# transponder-7_0_0.net
KiCad netlist of a schematic drawn in EAGLE
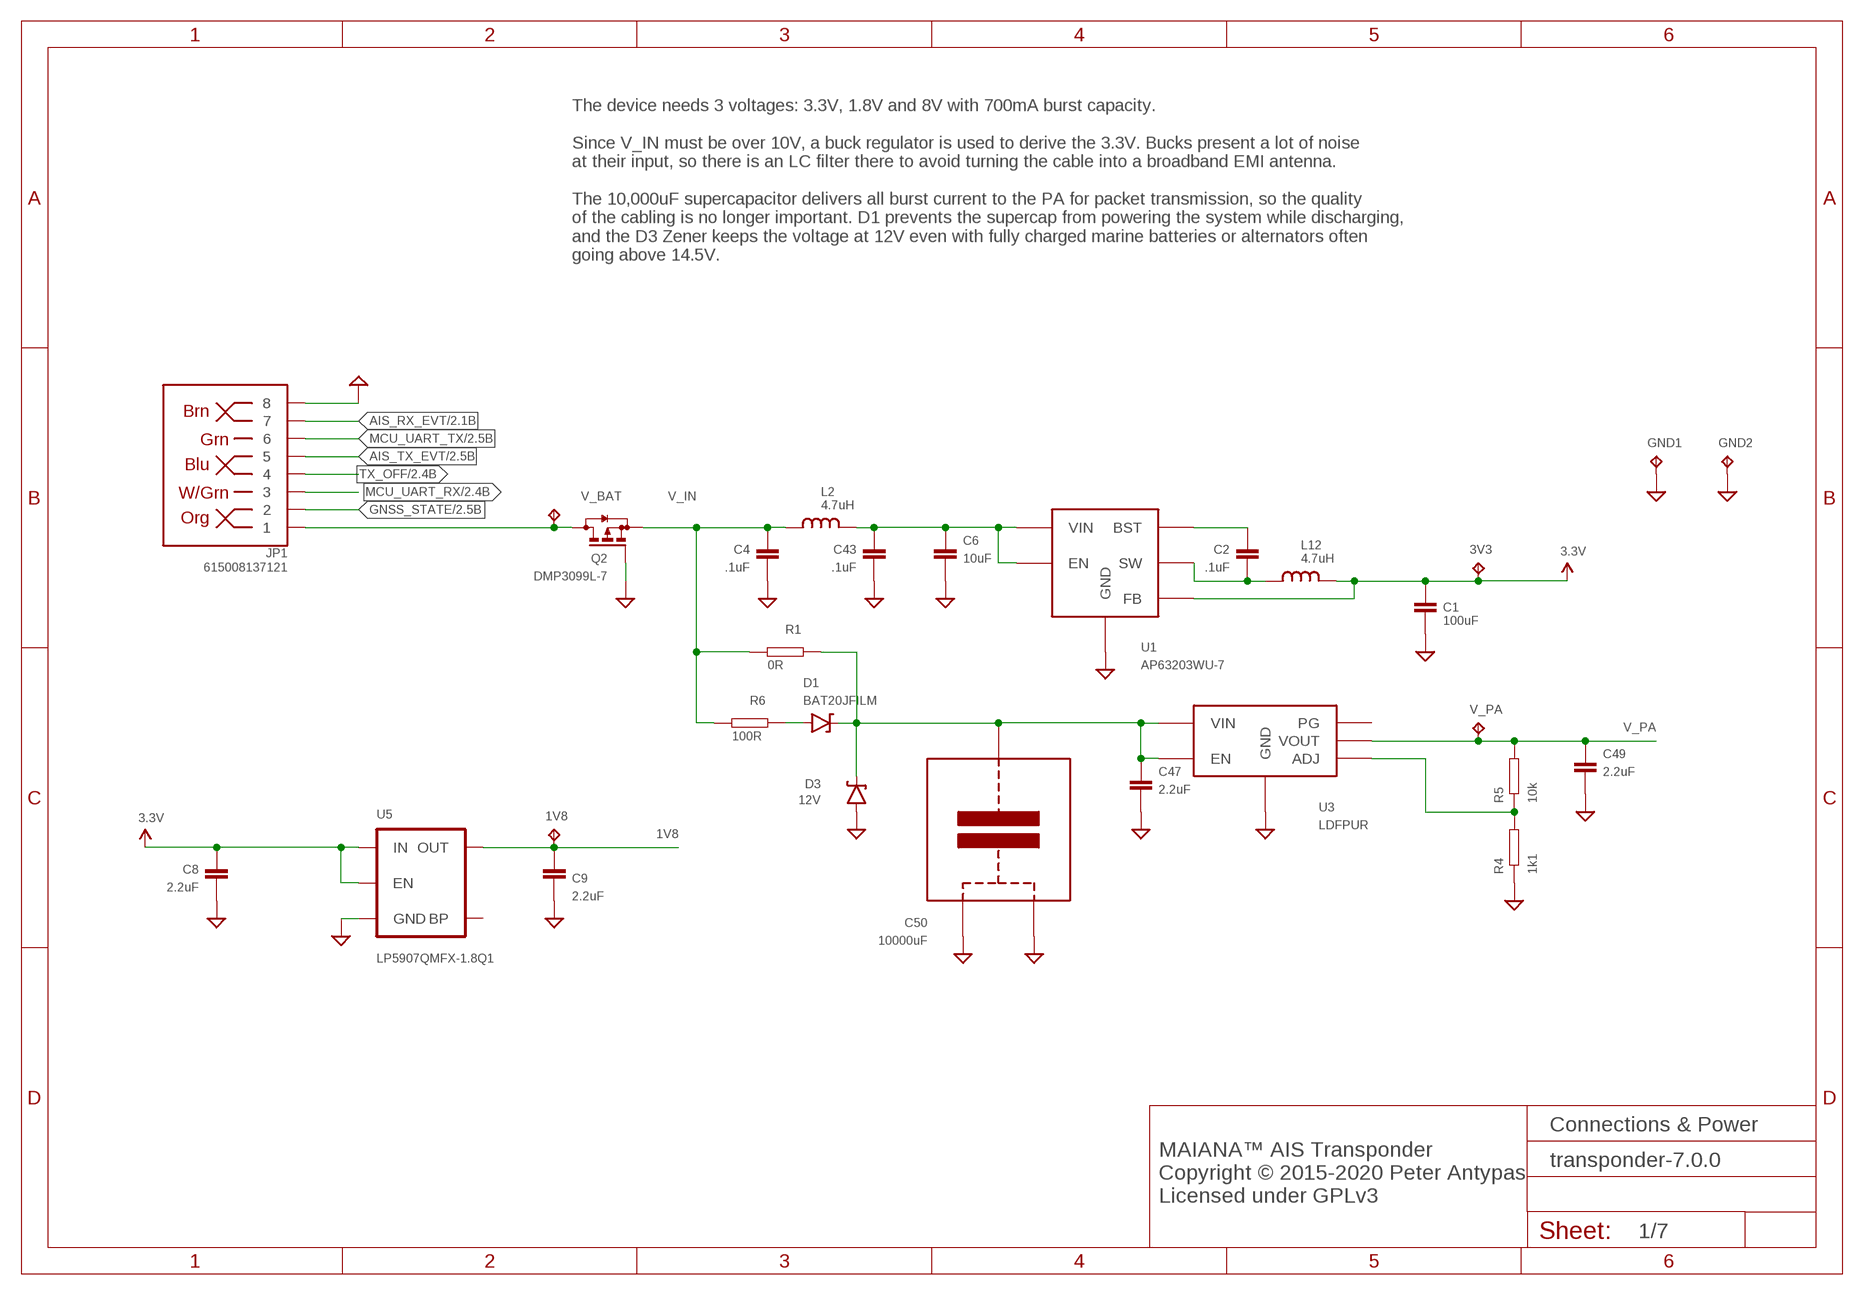
[diagram p0: schematic, sheet 1]
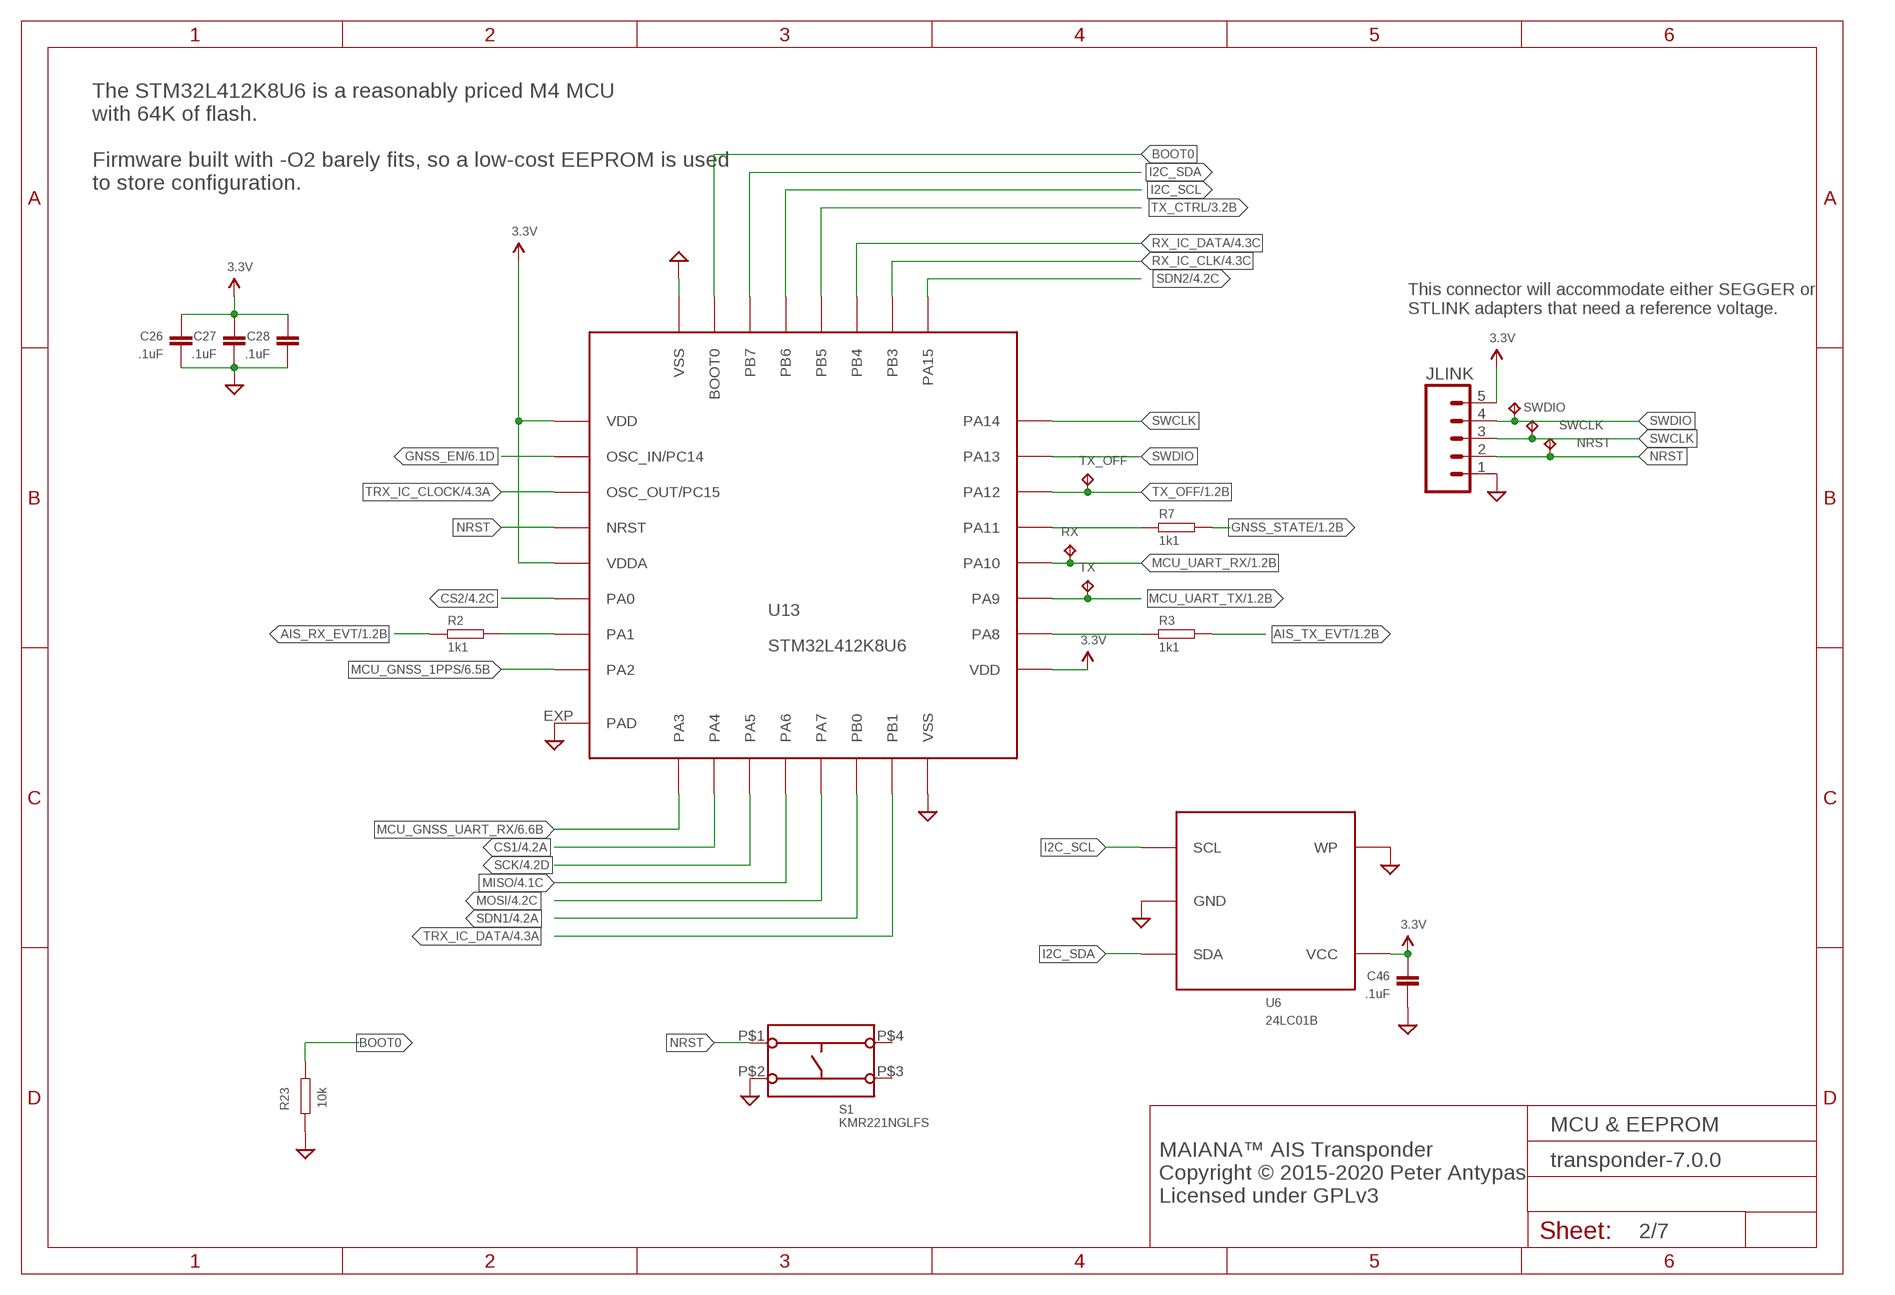
[diagram p1: schematic, sheet 2]
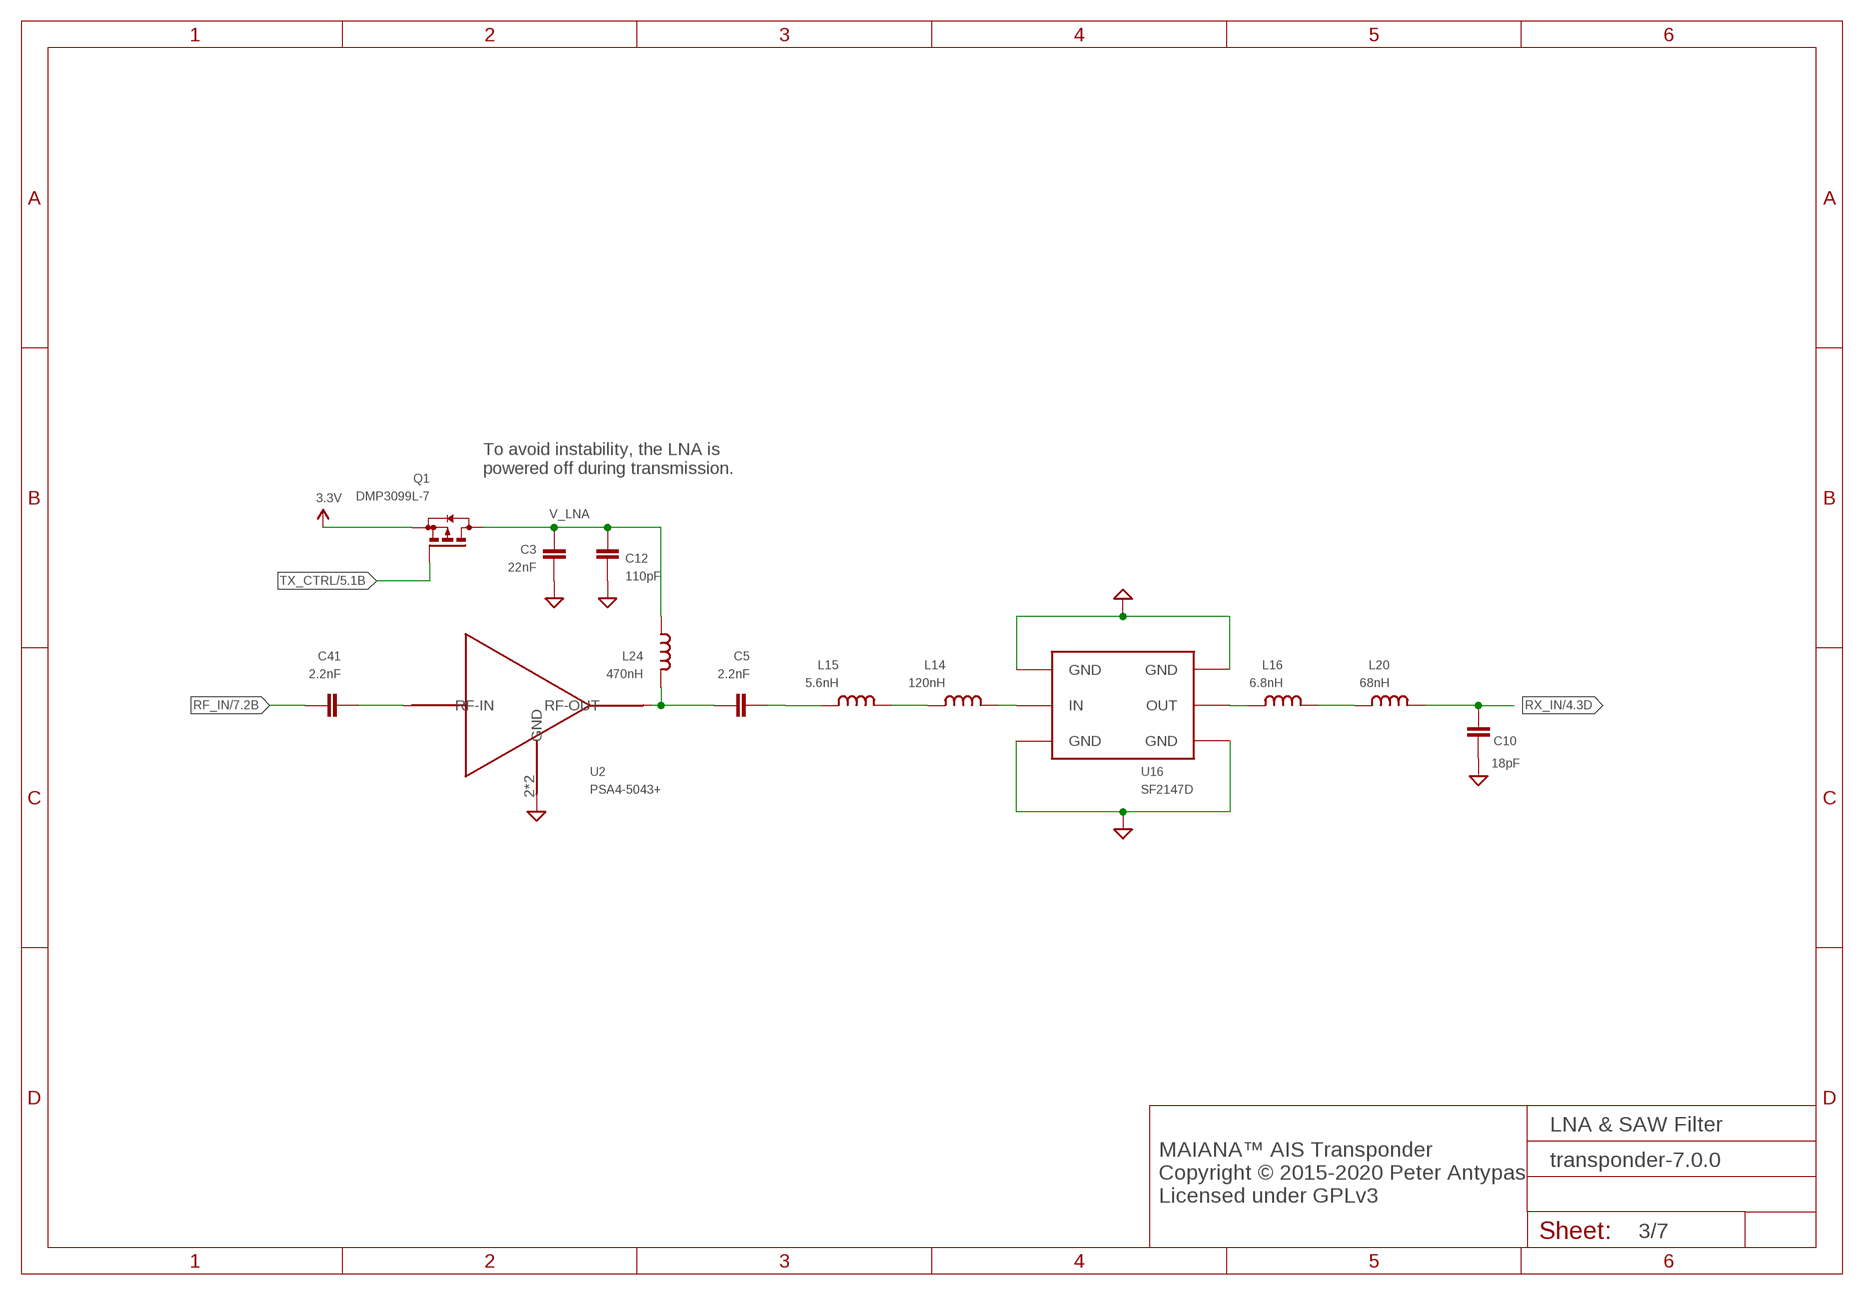
[diagram p2: schematic, sheet 3]
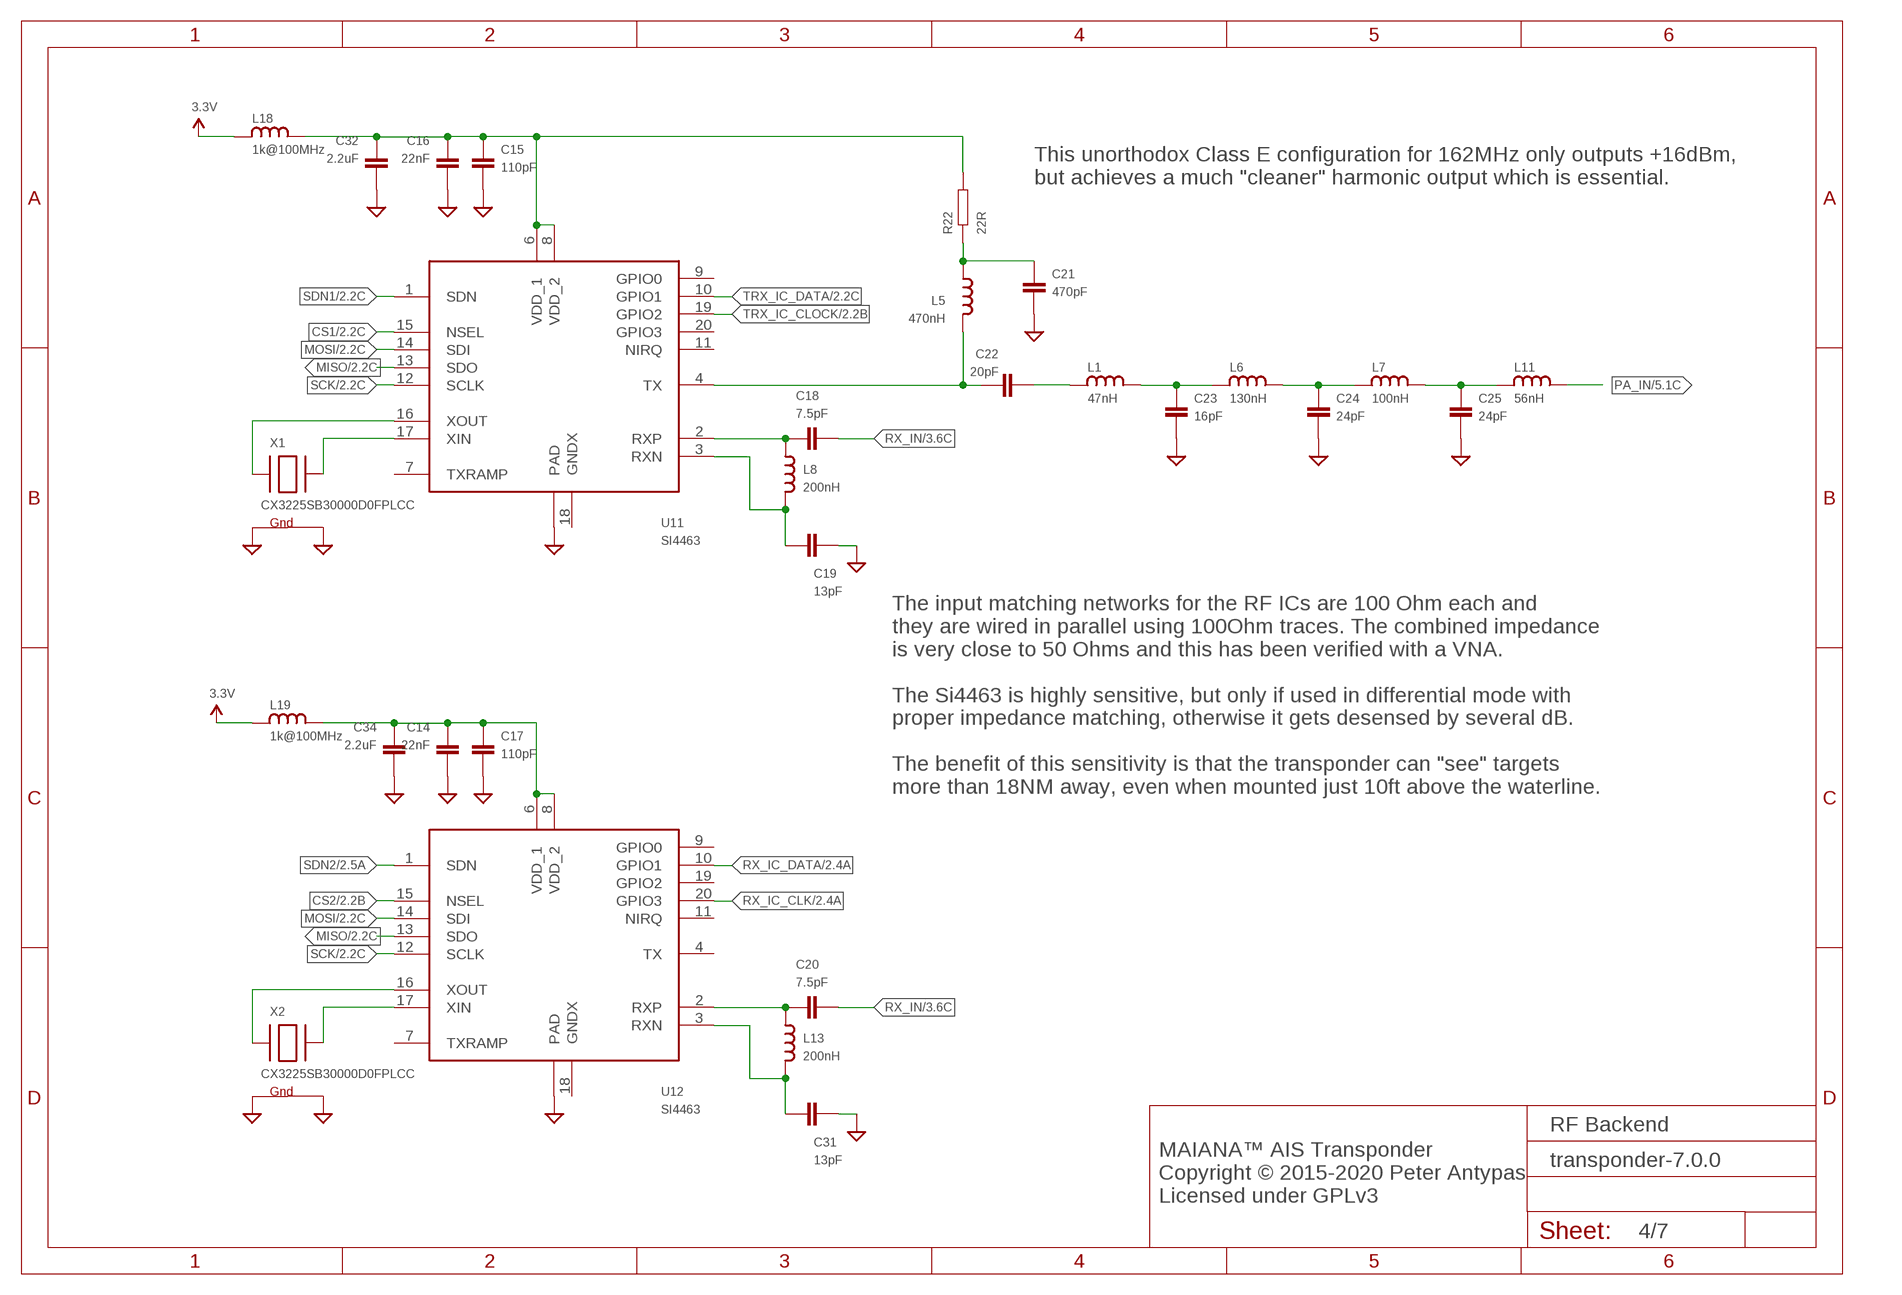
[diagram p3: schematic, sheet 4]
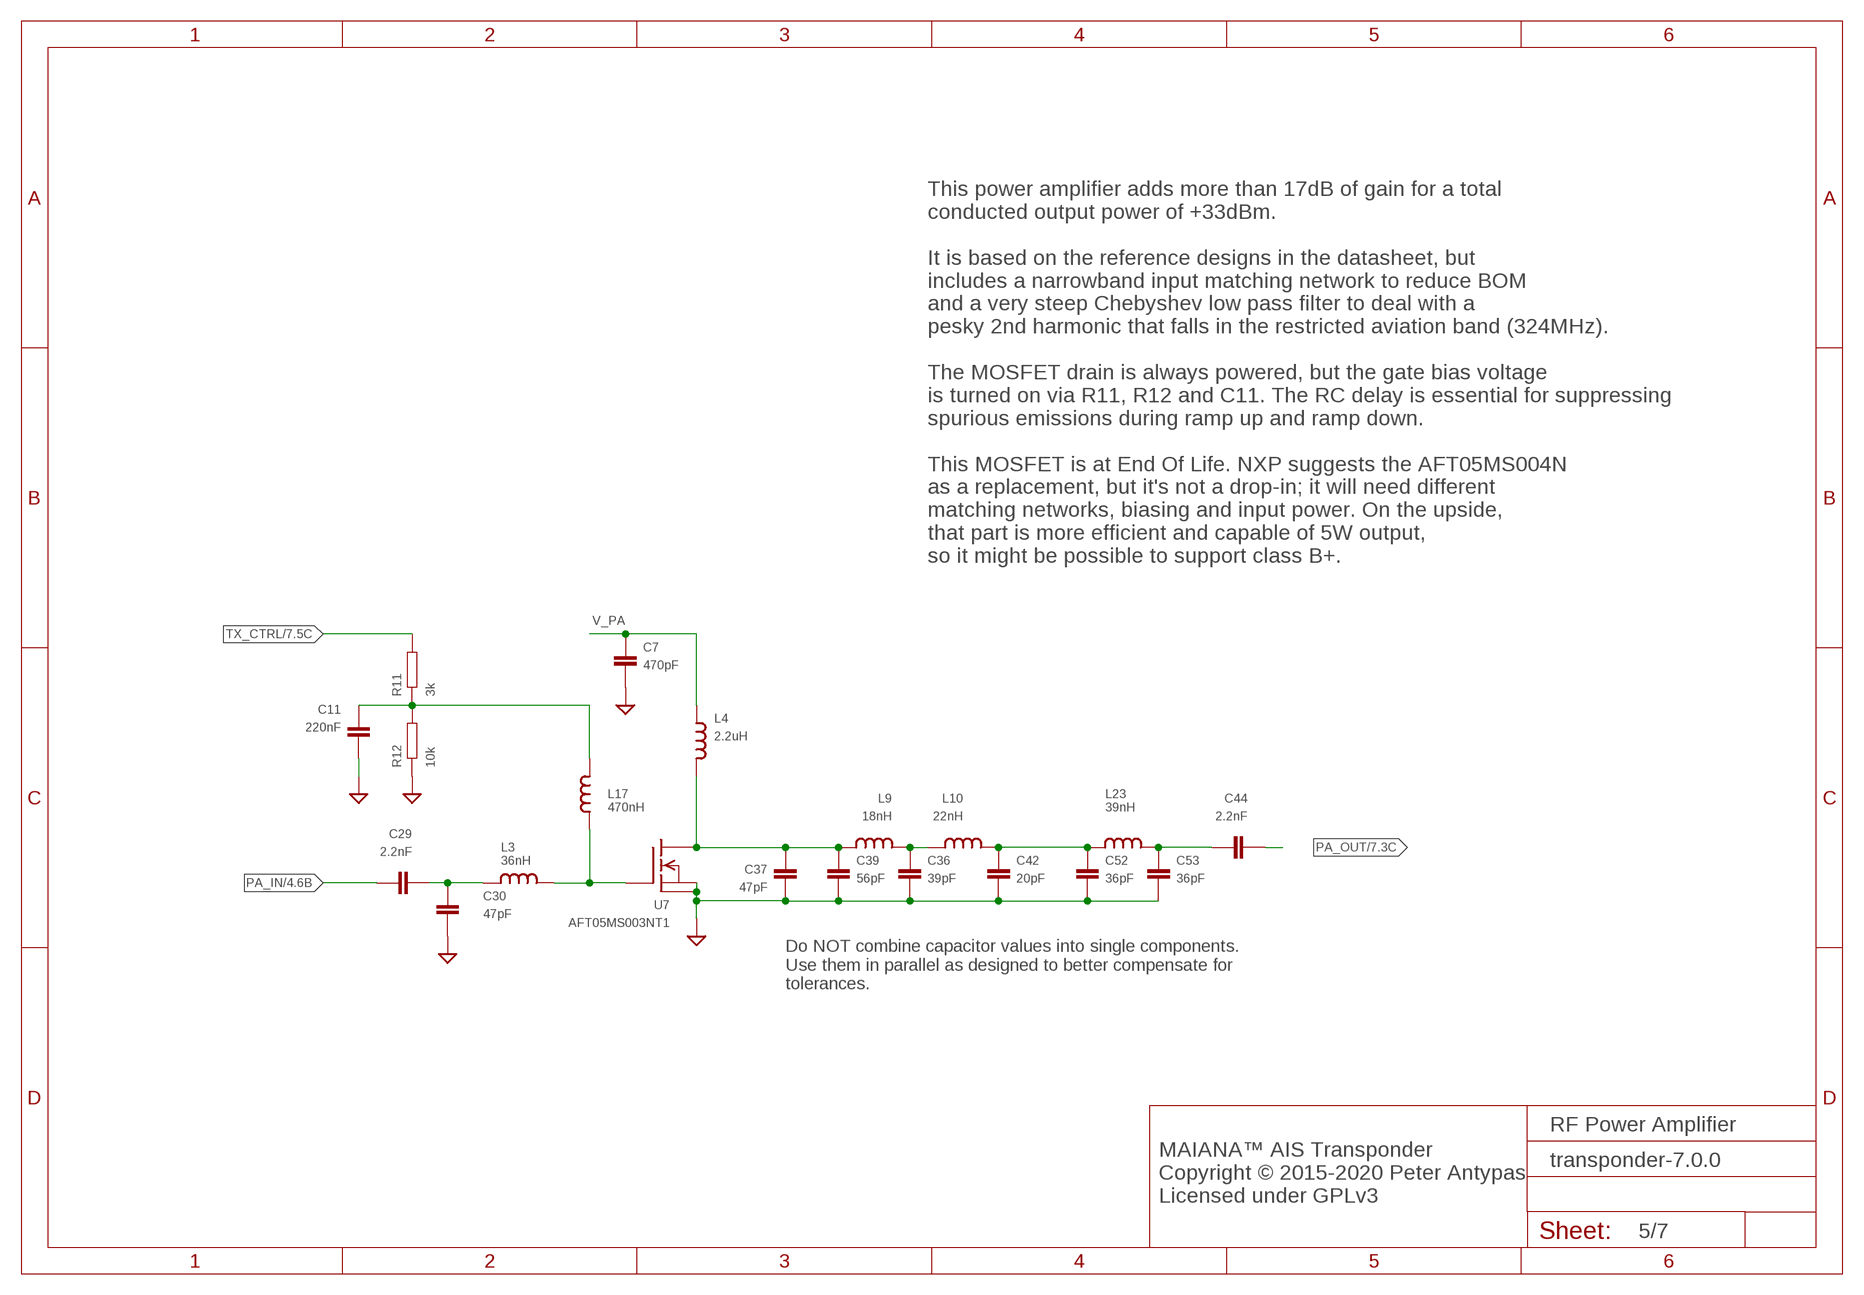
[diagram p4: schematic, sheet 5]
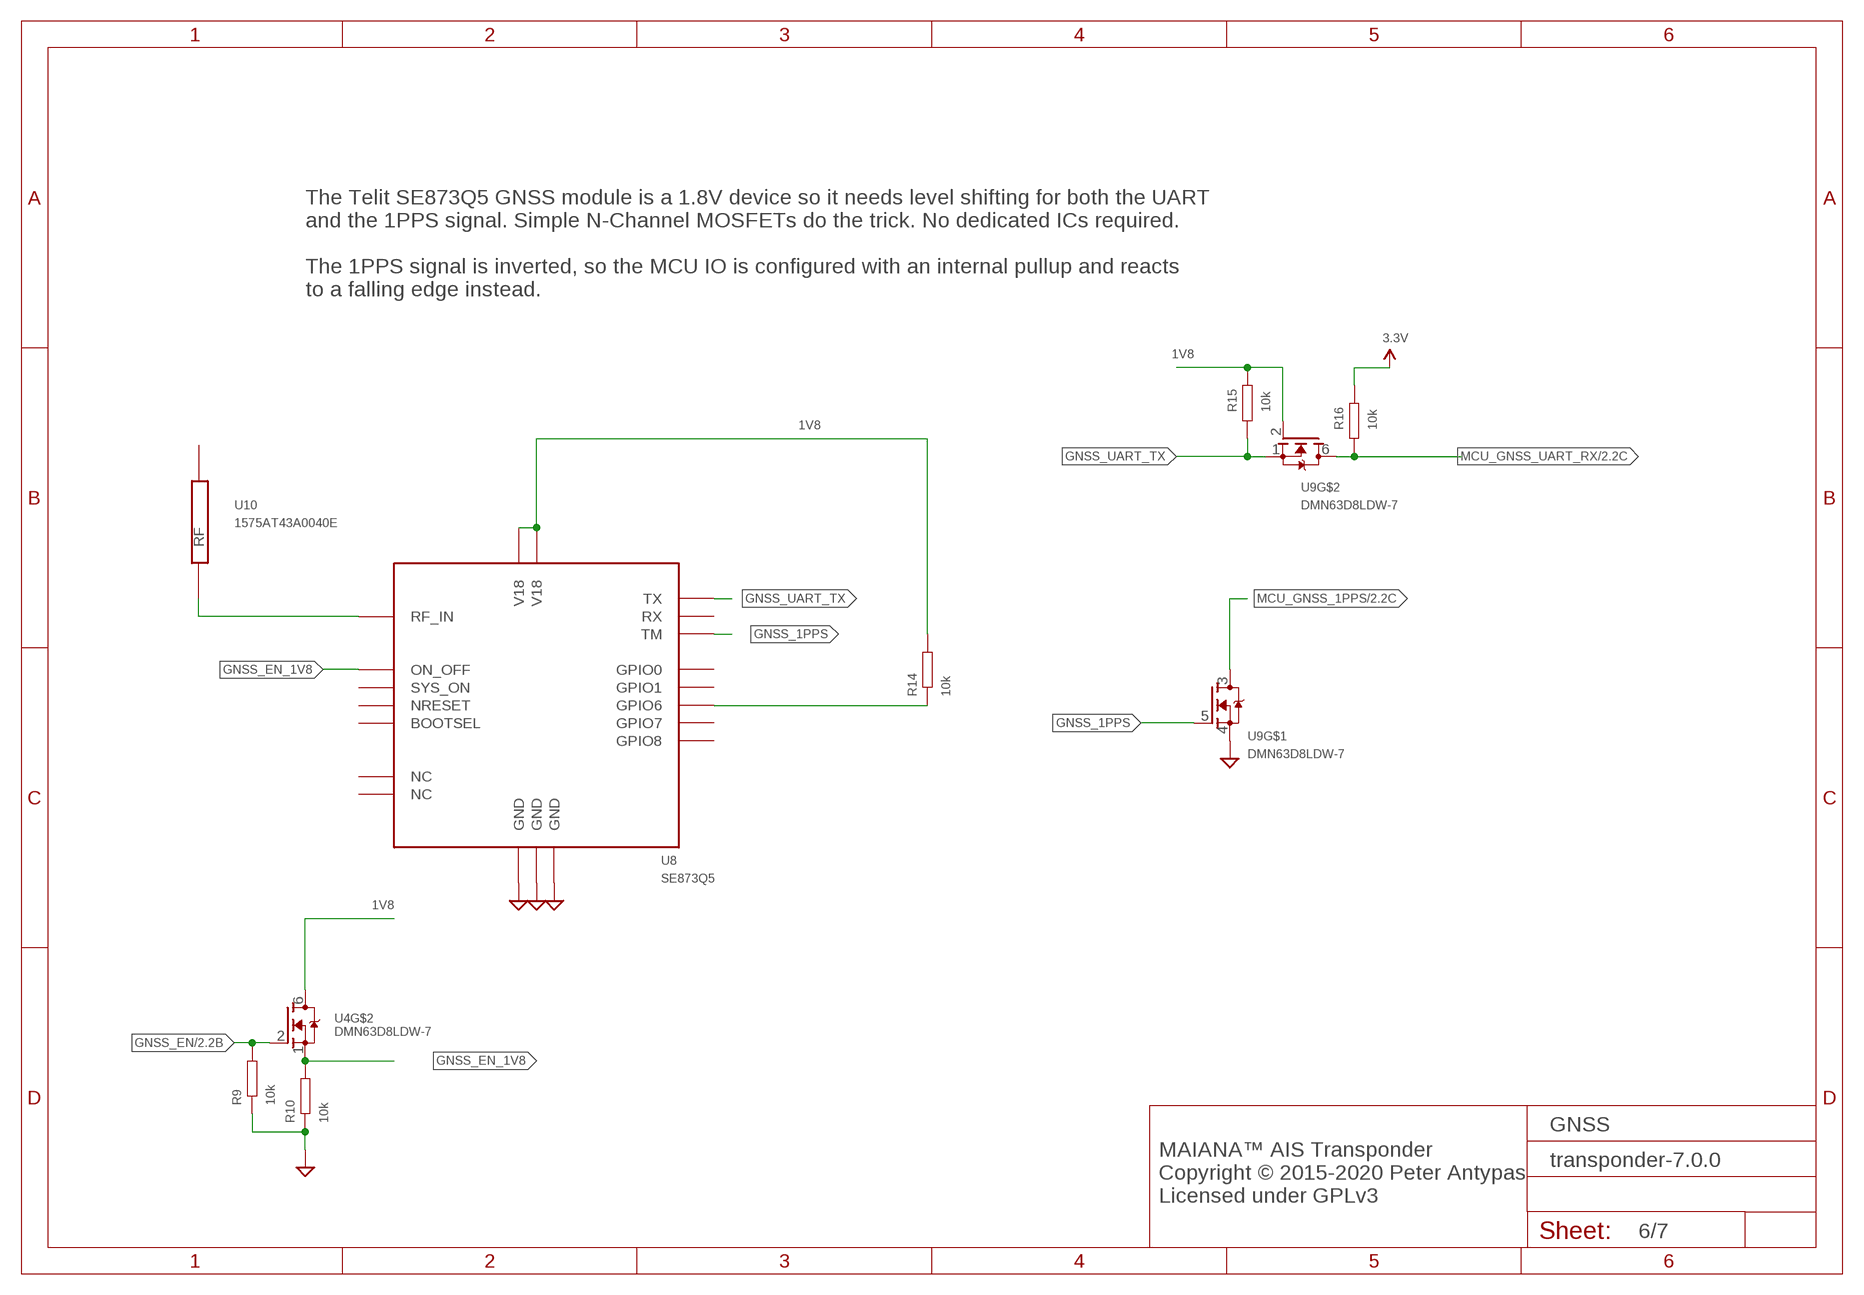
[diagram p5: schematic, sheet 6]
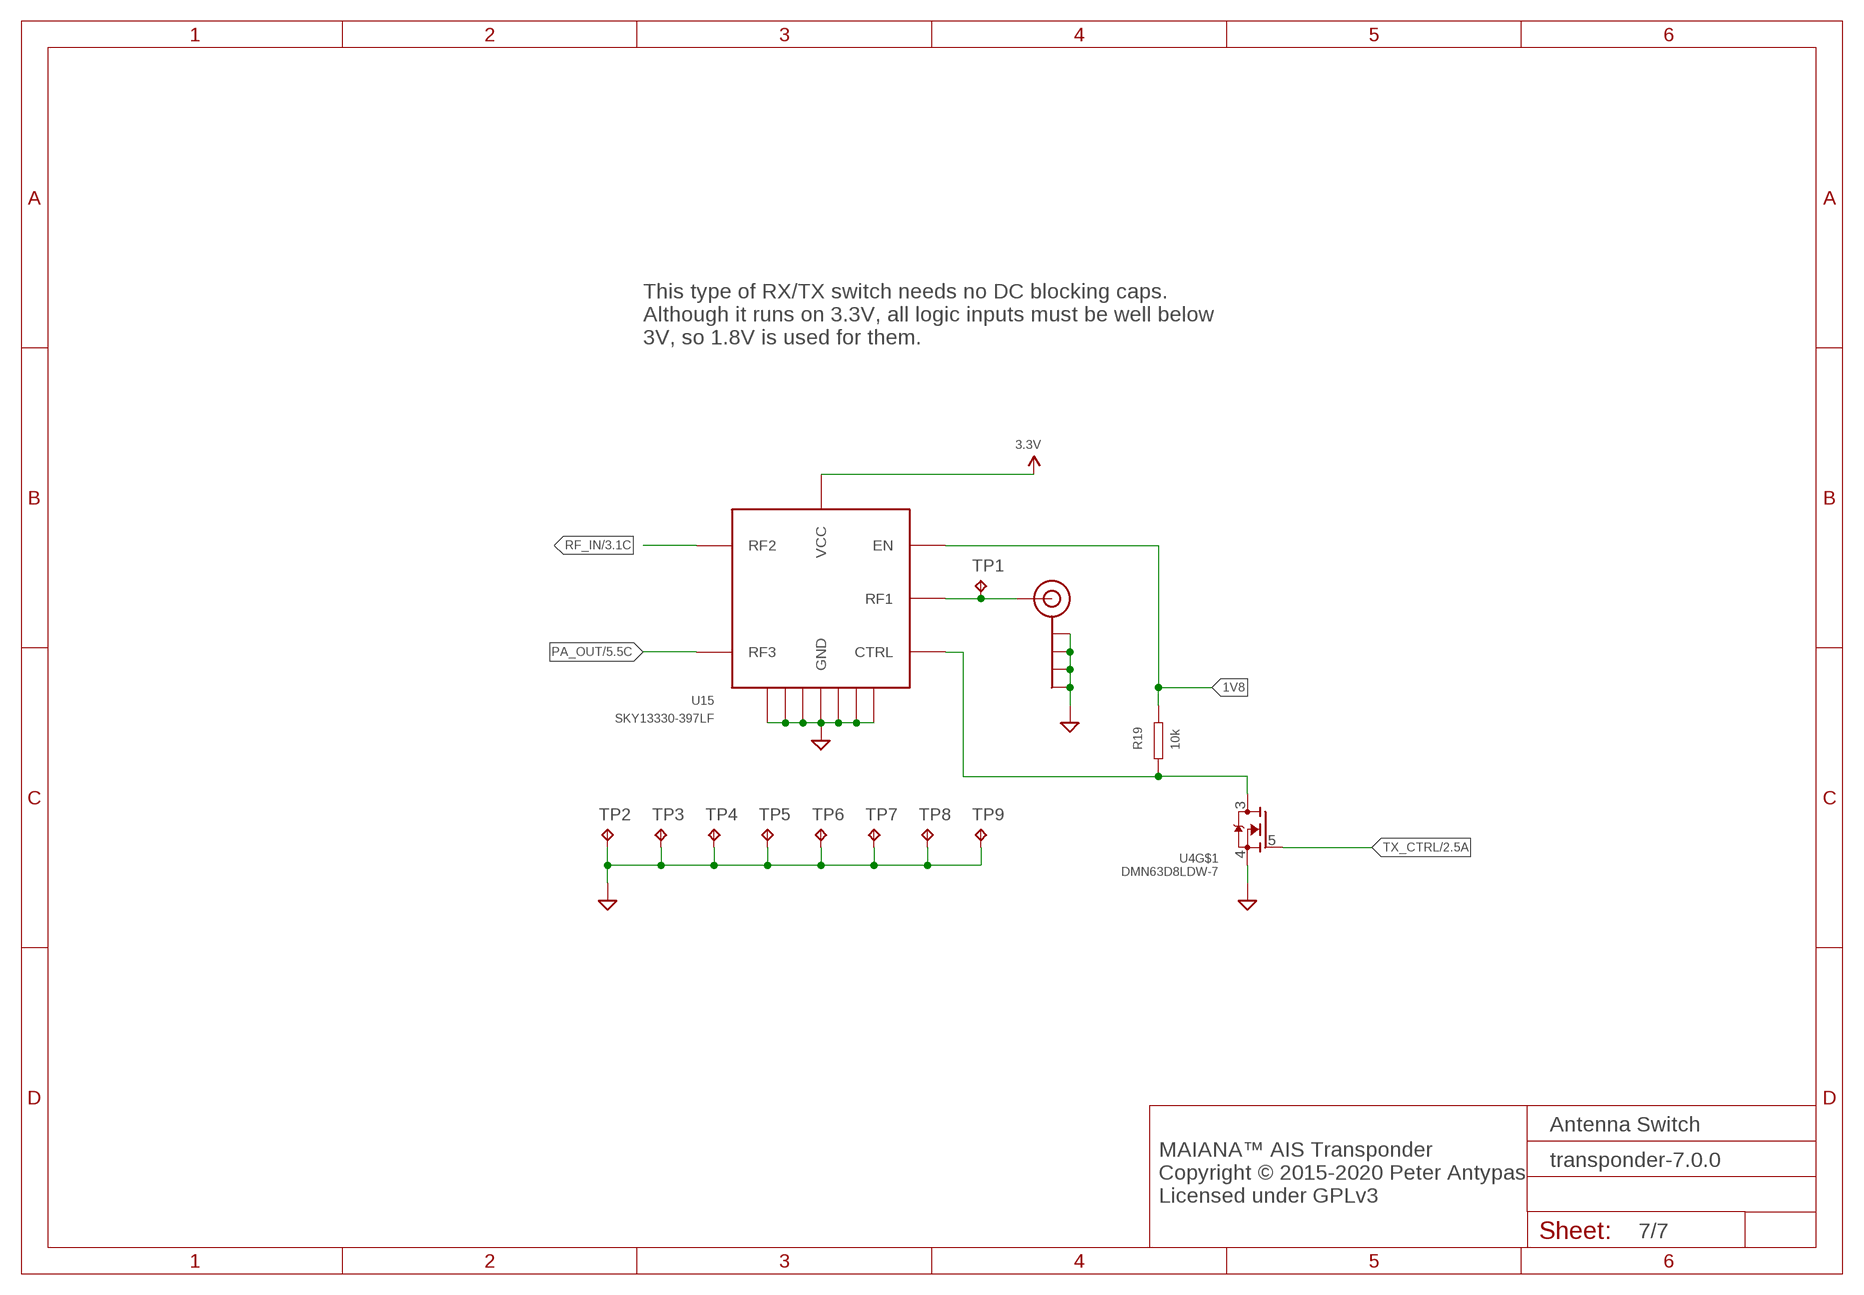
[diagram p6: schematic, sheet 7]

(export (version "E")
  (design (tool "Eeschema 10.0.6"))
  (components
    (comp (ref "1V8")
      (value "TPTP12R")
      (footprint "eagle-import:TP12R")
      (libsource (lib "eagle-import") (part "TPTP12R"))
    )
    (comp (ref "3V3")
      (value "TPTP12R")
      (footprint "eagle-import:TP12R")
      (libsource (lib "eagle-import") (part "TPTP12R"))
    )
    (comp (ref "C1")
      (value "100uF")
      (footprint "eagle-import:1206")
      (fields (field (name "PARTNO") "JMK316ABJ107ML-T"))
      (libsource (lib "eagle-import") (part "CAPACITOR1206"))
    )
    (comp (ref "C2")
      (value ".1uF")
      (footprint "eagle-import:0603")
      (fields (field (name "PARTNO") "EMK107B7104KAHT"))
      (libsource (lib "eagle-import") (part "CAPACITOR0603"))
    )
    (comp (ref "C4")
      (value ".1uF")
      (footprint "eagle-import:0603")
      (fields (field (name "PARTNO") "EMK107B7104KAHT"))
      (libsource (lib "eagle-import") (part "CAPACITOR0603"))
    )
    (comp (ref "C6")
      (value "10uF")
      (footprint "eagle-import:0805")
      (fields (field (name "PARTNO") " EMK212ABJ106KG-T"))
      (libsource (lib "eagle-import") (part "CAPACITOR0805"))
    )
    (comp (ref "C8")
      (value "2.2uF")
      (footprint "eagle-import:0603")
      (fields (field (name "PARTNO") "EMK107BJ225KA-T"))
      (libsource (lib "eagle-import") (part "CAPACITOR0603"))
    )
    (comp (ref "C9")
      (value "2.2uF")
      (footprint "eagle-import:0603")
      (fields (field (name "PARTNO") "EMK107BJ225KA-T"))
      (libsource (lib "eagle-import") (part "CAPACITOR0603"))
    )
    (comp (ref "C43")
      (value ".1uF")
      (footprint "eagle-import:0603")
      (fields (field (name "PARTNO") "EMK107B7104KAHT"))
      (libsource (lib "eagle-import") (part "CAPACITOR0603"))
    )
    (comp (ref "C47")
      (value "2.2uF")
      (footprint "eagle-import:0603")
      (fields (field (name "PARTNO") "EMK107BJ225KA-T"))
      (libsource (lib "eagle-import") (part "CAPACITOR0603"))
    )
    (comp (ref "C49")
      (value "2.2uF")
      (footprint "eagle-import:0603")
      (fields (field (name "PARTNO") "EMK107BJ225KA-T"))
      (libsource (lib "eagle-import") (part "CAPACITOR0603"))
    )
    (comp (ref "C50")
      (value "10000uF")
      (footprint "eagle-import:BZ05")
      (fields (field (name "PARTNO") "BZ05CA103ZSB"))
      (libsource (lib "eagle-import") (part "BZ05CA103ZSB"))
    )
    (comp (ref "D1")
      (value "BAT20JFILM")
      (footprint "eagle-import:SOD323")
      (fields (field (name "PARTNO") "BAT20JFILM"))
      (libsource (lib "eagle-import") (part "DIODE-SCHOTTKYSOD323"))
    )
    (comp (ref "D3")
      (value "12V")
      (footprint "eagle-import:SOD-323")
      (fields (field (name "PARTNO") "MM3Z12VST1G"))
      (libsource (lib "eagle-import") (part "DIODE-ZENER5.6V"))
    )
    (comp (ref "GND1")
      (value "TPTP16R")
      (footprint "eagle-import:TP16R")
      (libsource (lib "eagle-import") (part "TPTP16R"))
    )
    (comp (ref "GND2")
      (value "TPTP16R")
      (footprint "eagle-import:TP16R")
      (libsource (lib "eagle-import") (part "TPTP16R"))
    )
    (comp (ref "JP1")
      (value "615008137121")
      (footprint "eagle-import:RJ45-8")
      (fields (field (name "PARTNO") "‎615008137121‎"))
      (libsource (lib "eagle-import") (part "RJ45-8PTH"))
    )
    (comp (ref "L2")
      (value "4.7uH")
      (footprint "eagle-import:0805")
      (fields (field (name "PARTNO") "MLZ2012M4R7WT000"))
      (libsource (lib "eagle-import") (part "INDUCTOR0805"))
    )
    (comp (ref "L12")
      (value "4.7uH")
      (footprint "eagle-import:0805")
      (fields (field (name "PARTNO") "MLZ2012M4R7WT000"))
      (libsource (lib "eagle-import") (part "INDUCTOR0805"))
    )
    (comp (ref "Q2")
      (value "DMP3099L-7")
      (footprint "eagle-import:SOT23")
      (libsource (lib "eagle-import") (part "BSS84"))
    )
    (comp (ref "R1")
      (value "0R")
      (footprint "eagle-import:0603")
      (fields (field (name "PARTNO") "RC0603FR-070RL"))
      (libsource (lib "eagle-import") (part "RESISTOR0603"))
    )
    (comp (ref "R4")
      (value "1k1")
      (footprint "eagle-import:0603")
      (fields (field (name "PARTNO") "RC0603JR-071K1L"))
      (libsource (lib "eagle-import") (part "RESISTOR0603"))
    )
    (comp (ref "R5")
      (value "10k")
      (footprint "eagle-import:0603")
      (fields (field (name "PARTNO") "RC0603JR-0710KL"))
      (libsource (lib "eagle-import") (part "RESISTOR0603"))
    )
    (comp (ref "R6")
      (value "100R")
      (footprint "eagle-import:0603")
      (fields (field (name "PARTNO") "RC0603FR-07100RL"))
      (libsource (lib "eagle-import") (part "RESISTOR0603"))
    )
    (comp (ref "U1")
      (value "AP63203WU-7")
      (footprint "eagle-import:SOT23-6")
      (libsource (lib "eagle-import") (part "AP63203"))
    )
    (comp (ref "U3")
      (value "LDFPUR")
      (footprint "eagle-import:DFN-6")
      (libsource (lib "eagle-import") (part "LDF"))
    )
    (comp (ref "U5")
      (value "LP5907QMFX-1.8Q1")
      (footprint "eagle-import:SOT23-5")
      (fields (field (name "PARTNO") "LP5907QMFX-1.8Q1 "))
      (libsource (lib "eagle-import") (part "V_REG_LDOSMD"))
    )
    (comp (ref "V_BAT")
      (value "TPTP12R")
      (footprint "eagle-import:TP12R")
      (libsource (lib "eagle-import") (part "TPTP12R"))
    )
    (comp (ref "V_PA")
      (value "TPTP12R")
      (footprint "eagle-import:TP12R")
      (libsource (lib "eagle-import") (part "TPTP12R"))
    )
    (comp (ref "C3")
      (value "22nF")
      (footprint "eagle-import:0603")
      (fields (field (name "PARTNO") "GRM188R71E223KA01D"))
      (libsource (lib "eagle-import") (part "CAPACITOR0603"))
    )
    (comp (ref "C5")
      (value "2.2nF")
      (footprint "eagle-import:0603")
      (fields (field (name "PARTNO") "GRM1885C1H222JA01J"))
      (libsource (lib "eagle-import") (part "CAPACITOR0603"))
    )
    (comp (ref "C10")
      (value "18pF")
      (footprint "eagle-import:0603")
      (fields (field (name "PARTNO") "06035A180JAT4A"))
      (libsource (lib "eagle-import") (part "CAPACITOR0603"))
    )
    (comp (ref "C12")
      (value "110pF")
      (footprint "eagle-import:0603")
      (fields (field (name "PARTNO") "GRM1885C2A111JA01D"))
      (libsource (lib "eagle-import") (part "CAPACITOR0603"))
    )
    (comp (ref "C41")
      (value "2.2nF")
      (footprint "eagle-import:0603")
      (fields (field (name "PARTNO") "GRM1885C1H222JA01J"))
      (libsource (lib "eagle-import") (part "CAPACITOR0603"))
    )
    (comp (ref "L14")
      (value "120nH")
      (footprint "eagle-import:0603")
      (fields (field (name "PARTNO") "LQW18ASR12G0ZD"))
      (libsource (lib "eagle-import") (part "INDUCTOR0603"))
    )
    (comp (ref "L15")
      (value "5.6nH")
      (footprint "eagle-import:0603")
      (fields (field (name "PARTNO") "LQW18AN5N6G8ZD"))
      (libsource (lib "eagle-import") (part "INDUCTOR0603"))
    )
    (comp (ref "L16")
      (value "6.8nH")
      (footprint "eagle-import:0603")
      (fields (field (name "PARTNO") "LQW18AN6N8C10D"))
      (libsource (lib "eagle-import") (part "INDUCTOR0603"))
    )
    (comp (ref "L20")
      (value "68nH")
      (footprint "eagle-import:0603")
      (fields (field (name "PARTNO") "LQW18AN68NG00D"))
      (libsource (lib "eagle-import") (part "INDUCTOR0603"))
    )
    (comp (ref "L24")
      (value "470nH")
      (footprint "eagle-import:0603")
      (fields (field (name "PARTNO") "HK1608R47J-T"))
      (libsource (lib "eagle-import") (part "INDUCTOR0603"))
    )
    (comp (ref "Q1")
      (value "DMP3099L-7")
      (footprint "eagle-import:SOT23")
      (libsource (lib "eagle-import") (part "BSS84"))
    )
    (comp (ref "U2")
      (value "PSA4-5043+")
      (footprint "eagle-import:PSA4-5043+")
      (fields (field (name "MF") "Mini-Circuits"))
      (libsource (lib "eagle-import") (part "PSA4-5043+"))
    )
    (comp (ref "U16")
      (value "SF2147D")
      (footprint "eagle-import:SAW_FILTER1")
      (libsource (lib "eagle-import") (part "SF2147D"))
    )
    (comp (ref "C14")
      (value "22nF")
      (footprint "eagle-import:0603")
      (fields (field (name "PARTNO") "GRM188R71E223KA01D"))
      (libsource (lib "eagle-import") (part "CAPACITOR0603"))
    )
    (comp (ref "C15")
      (value "110pF")
      (footprint "eagle-import:0603")
      (fields (field (name "PARTNO") "GRM1885C2A111JA01D"))
      (libsource (lib "eagle-import") (part "CAPACITOR0603"))
    )
    (comp (ref "C16")
      (value "22nF")
      (footprint "eagle-import:0603")
      (fields (field (name "PARTNO") "GRM188R71E223KA01D"))
      (libsource (lib "eagle-import") (part "CAPACITOR0603"))
    )
    (comp (ref "C17")
      (value "110pF")
      (footprint "eagle-import:0603")
      (fields (field (name "PARTNO") "GRM1885C2A111JA01D"))
      (libsource (lib "eagle-import") (part "CAPACITOR0603"))
    )
    (comp (ref "C18")
      (value "7.5pF")
      (footprint "eagle-import:0603")
      (fields (field (name "PARTNO") "GRM1885C1H7R5DA01D"))
      (libsource (lib "eagle-import") (part "CAPACITOR0603"))
    )
    (comp (ref "C19")
      (value "13pF")
      (footprint "eagle-import:0603")
      (fields (field (name "PARTNO") "GRM1885C1H130JA01D"))
      (libsource (lib "eagle-import") (part "CAPACITOR0603"))
    )
    (comp (ref "C20")
      (value "7.5pF")
      (footprint "eagle-import:0603")
      (fields (field (name "PARTNO") "GRM1885C1H7R5DA01D"))
      (libsource (lib "eagle-import") (part "CAPACITOR0603"))
    )
    (comp (ref "C21")
      (value "470pF")
      (footprint "eagle-import:0603")
      (fields (field (name "PARTNO") "GRM1885C1H471JA01D"))
      (libsource (lib "eagle-import") (part "CAPACITOR0603"))
    )
    (comp (ref "C22")
      (value "20pF")
      (footprint "eagle-import:0603")
      (fields (field (name "PARTNO") "GRM1885C1H200JA01D"))
      (libsource (lib "eagle-import") (part "CAPACITOR0603"))
    )
    (comp (ref "C23")
      (value "16pF")
      (footprint "eagle-import:0603")
      (fields (field (name "PARTNO") "GCM1885C2A160JA16D"))
      (libsource (lib "eagle-import") (part "CAPACITOR0603"))
    )
    (comp (ref "C24")
      (value "24pF")
      (footprint "eagle-import:0603")
      (fields (field (name "PARTNO") "GRM1885C2A240JA01D"))
      (libsource (lib "eagle-import") (part "CAPACITOR0603"))
    )
    (comp (ref "C25")
      (value "24pF")
      (footprint "eagle-import:0603")
      (fields (field (name "PARTNO") "GRM1885C2A240JA01D"))
      (libsource (lib "eagle-import") (part "CAPACITOR0603"))
    )
    (comp (ref "C31")
      (value "13pF")
      (footprint "eagle-import:0603")
      (fields (field (name "PARTNO") "GRM1885C1H130JA01D"))
      (libsource (lib "eagle-import") (part "CAPACITOR0603"))
    )
    (comp (ref "C32")
      (value "2.2uF")
      (footprint "eagle-import:0603")
      (fields (field (name "PARTNO") "EMK107BJ225KA-T"))
      (libsource (lib "eagle-import") (part "CAPACITOR0603"))
    )
    (comp (ref "C34")
      (value "2.2uF")
      (footprint "eagle-import:0603")
      (fields (field (name "PARTNO") "EMK107BJ225KA-T"))
      (libsource (lib "eagle-import") (part "CAPACITOR0603"))
    )
    (comp (ref "L1")
      (value "47nH")
      (footprint "eagle-import:0603")
      (fields (field (name "PARTNO") "LQW18AN47NG00D"))
      (libsource (lib "eagle-import") (part "INDUCTOR0603"))
    )
    (comp (ref "L5")
      (value "470nH")
      (footprint "eagle-import:0603")
      (fields (field (name "PARTNO") "HK1608R47J-T"))
      (libsource (lib "eagle-import") (part "INDUCTOR0603"))
    )
    (comp (ref "L6")
      (value "130nH")
      (footprint "eagle-import:0603")
      (fields (field (name "PARTNO") "LQW18ANR13G00D"))
      (libsource (lib "eagle-import") (part "INDUCTOR0603"))
    )
    (comp (ref "L7")
      (value "100nH")
      (footprint "eagle-import:0603")
      (fields (field (name "PARTNO") "LQW18ANR10G00D"))
      (libsource (lib "eagle-import") (part "INDUCTOR0603"))
    )
    (comp (ref "L8")
      (value "200nH")
      (footprint "eagle-import:0603")
      (fields (field (name "PARTNO") "LQW18ANR20J00D"))
      (libsource (lib "eagle-import") (part "INDUCTOR0603"))
    )
    (comp (ref "L11")
      (value "56nH")
      (footprint "eagle-import:0603")
      (fields (field (name "PARTNO") "LQW18AN56NG00D"))
      (libsource (lib "eagle-import") (part "INDUCTOR0603"))
    )
    (comp (ref "L13")
      (value "200nH")
      (footprint "eagle-import:0603")
      (fields (field (name "PARTNO") "LQW18ANR20J00D"))
      (libsource (lib "eagle-import") (part "INDUCTOR0603"))
    )
    (comp (ref "L18")
      (value "1k@100MHz")
      (footprint "eagle-import:0603")
      (fields (field (name "PARTNO") "MPZ1608S102ATA00"))
      (libsource (lib "eagle-import") (part "INDUCTOR0603"))
    )
    (comp (ref "L19")
      (value "1k@100MHz")
      (footprint "eagle-import:0603")
      (fields (field (name "PARTNO") "MPZ1608S102ATA00"))
      (libsource (lib "eagle-import") (part "INDUCTOR0603"))
    )
    (comp (ref "R22")
      (value "22R")
      (footprint "eagle-import:0603")
      (fields (field (name "PARTNO") "RC0603JR-0722RL"))
      (libsource (lib "eagle-import") (part "RESISTOR0603"))
    )
    (comp (ref "U11")
      (value "SI4463")
      (footprint "eagle-import:SI4463")
      (fields (field (name "PARTNO") "SI4463-C2A-GMR"))
      (libsource (lib "eagle-import") (part "SI4463"))
    )
    (comp (ref "U12")
      (value "SI4463")
      (footprint "eagle-import:SI4463")
      (fields (field (name "PARTNO") "SI4463-C2A-GMR"))
      (libsource (lib "eagle-import") (part "SI4463"))
    )
    (comp (ref "X1")
      (value "CX3225SB30000D0FPLCC")
      (footprint "eagle-import:NX3225")
      (libsource (lib "eagle-import") (part "XTAL-4-3225"))
    )
    (comp (ref "X2")
      (value "CX3225SB30000D0FPLCC")
      (footprint "eagle-import:NX3225")
      (libsource (lib "eagle-import") (part "XTAL-4-3225"))
    )
    (comp (ref "C7")
      (value "470pF")
      (footprint "eagle-import:0603")
      (fields (field (name "PARTNO") "GRM1885C1H471JA01D"))
      (libsource (lib "eagle-import") (part "CAPACITOR0603"))
    )
    (comp (ref "C11")
      (value "220nF")
      (footprint "eagle-import:0603")
      (fields (field (name "PARTNO") "C0603C224K4RECAUTO"))
      (libsource (lib "eagle-import") (part "CAPACITOR0603"))
    )
    (comp (ref "C29")
      (value "2.2nF")
      (footprint "eagle-import:0603")
      (fields (field (name "PARTNO") "GRM1885C1H222JA01J"))
      (libsource (lib "eagle-import") (part "CAPACITOR0603"))
    )
    (comp (ref "C30")
      (value "47pF")
      (footprint "eagle-import:0603")
      (fields (field (name "PARTNO") "GRM1885C1H470JA01J"))
      (libsource (lib "eagle-import") (part "CAPACITOR0603"))
    )
    (comp (ref "C36")
      (value "39pF")
      (footprint "eagle-import:0603")
      (fields (field (name "PARTNO") "GRM1885C1H390JA01D"))
      (libsource (lib "eagle-import") (part "CAPACITOR0603"))
    )
    (comp (ref "C37")
      (value "47pF")
      (footprint "eagle-import:0603")
      (fields (field (name "PARTNO") "GRM1885C1H470JA01J"))
      (libsource (lib "eagle-import") (part "CAPACITOR0603"))
    )
    (comp (ref "C39")
      (value "56pF")
      (footprint "eagle-import:0603")
      (fields (field (name "PARTNO") "GRM1885C1H560JA01D"))
      (libsource (lib "eagle-import") (part "CAPACITOR0603"))
    )
    (comp (ref "C42")
      (value "20pF")
      (footprint "eagle-import:0603")
      (fields (field (name "PARTNO") "GRM1885C1H200JA01D"))
      (libsource (lib "eagle-import") (part "CAPACITOR0603"))
    )
    (comp (ref "C44")
      (value "2.2nF")
      (footprint "eagle-import:0603")
      (fields (field (name "PARTNO") "GRM1885C1H222JA01J"))
      (libsource (lib "eagle-import") (part "CAPACITOR0603"))
    )
    (comp (ref "C52")
      (value "36pF")
      (footprint "eagle-import:0603")
      (fields (field (name "PARTNO") "06035A360JAT2A"))
      (libsource (lib "eagle-import") (part "CAPACITOR0603"))
    )
    (comp (ref "C53")
      (value "36pF")
      (footprint "eagle-import:0603")
      (fields (field (name "PARTNO") "06035A360JAT2A"))
      (libsource (lib "eagle-import") (part "CAPACITOR0603"))
    )
    (comp (ref "L3")
      (value "36nH")
      (footprint "eagle-import:0603")
      (fields (field (name "PARTNO") "LQW18AN36NG00D"))
      (libsource (lib "eagle-import") (part "INDUCTOR0603"))
    )
    (comp (ref "L4")
      (value "2.2uH")
      (footprint "eagle-import:0805")
      (fields (field (name "PARTNO") "BRC2012T2R2MD"))
      (libsource (lib "eagle-import") (part "INDUCTOR0805"))
    )
    (comp (ref "L9")
      (value "18nH")
      (footprint "eagle-import:0603")
      (fields (field (name "PARTNO") "LQW18AN18NG00D"))
      (libsource (lib "eagle-import") (part "INDUCTOR0603"))
    )
    (comp (ref "L10")
      (value "22nH")
      (footprint "eagle-import:0603")
      (fields (field (name "PARTNO") "LQW18AN22NJ00D"))
      (libsource (lib "eagle-import") (part "INDUCTOR0603"))
    )
    (comp (ref "L17")
      (value "470nH")
      (footprint "eagle-import:0603")
      (fields (field (name "PARTNO") "HK1608R47J-T"))
      (libsource (lib "eagle-import") (part "INDUCTOR0603"))
    )
    (comp (ref "L23")
      (value "39nH")
      (footprint "eagle-import:0603")
      (fields (field (name "PARTNO") "LQW18AN39NG00D"))
      (libsource (lib "eagle-import") (part "INDUCTOR0603"))
    )
    (comp (ref "R11")
      (value "3k")
      (footprint "eagle-import:0603")
      (fields (field (name "PARTNO") "RC0603JR-073KL"))
      (libsource (lib "eagle-import") (part "RESISTOR0603"))
    )
    (comp (ref "R12")
      (value "10k")
      (footprint "eagle-import:0603")
      (fields (field (name "PARTNO") "RC0603JR-0710KL"))
      (libsource (lib "eagle-import") (part "RESISTOR0603"))
    )
    (comp (ref "U7")
      (value "AFT05MS003NT1")
      (footprint "eagle-import:SOT-89")
      (libsource (lib "eagle-import") (part "AFT0SMS003N"))
    )
    (comp (ref "R9")
      (value "10k")
      (footprint "eagle-import:0603")
      (fields (field (name "PARTNO") "RC0603JR-0710KL"))
      (libsource (lib "eagle-import") (part "RESISTOR0603"))
    )
    (comp (ref "R10")
      (value "10k")
      (footprint "eagle-import:0603")
      (fields (field (name "PARTNO") "RC0603JR-0710KL"))
      (libsource (lib "eagle-import") (part "RESISTOR0603"))
    )
    (comp (ref "R14")
      (value "10k")
      (footprint "eagle-import:0603")
      (fields (field (name "PARTNO") "RC0603JR-0710KL"))
      (libsource (lib "eagle-import") (part "RESISTOR0603"))
    )
    (comp (ref "R15")
      (value "10k")
      (footprint "eagle-import:0603")
      (fields (field (name "PARTNO") "RC0603JR-0710KL"))
      (libsource (lib "eagle-import") (part "RESISTOR0603"))
    )
    (comp (ref "R16")
      (value "10k")
      (footprint "eagle-import:0603")
      (fields (field (name "PARTNO") "RC0603JR-0710KL"))
      (libsource (lib "eagle-import") (part "RESISTOR0603"))
    )
    (comp (ref "U4")
      (value "DMN63D8LDW-7")
      (footprint "eagle-import:SOT363")
      (fields (field (name "PARTNO") "DMN63D8LDW-7"))
      (libsource (lib "eagle-import") (part "DMN63D8LDW"))
    )
    (comp (ref "U8")
      (value "SE873Q5")
      (footprint "eagle-import:SE873")
      (libsource (lib "eagle-import") (part "SE873"))
    )
    (comp (ref "U9")
      (value "DMN63D8LDW-7")
      (footprint "eagle-import:SOT363")
      (fields (field (name "PARTNO") "DMN63D8LDW-7"))
      (libsource (lib "eagle-import") (part "DMN63D8LDW"))
    )
    (comp (ref "U10")
      (value "1575AT43A0040E")
      (footprint "eagle-import:1575AT43A0040E")
      (libsource (lib "eagle-import") (part "1575AT43A0040E"))
    )
    (comp (ref "J$1")
      (value "SMA_EDGE")
      (footprint "eagle-import:SMA-EDGE")
      (libsource (lib "eagle-import") (part "SMA_EDGE"))
    )
    (comp (ref "R19")
      (value "10k")
      (footprint "eagle-import:0603")
      (fields (field (name "PARTNO") "RC0603JR-0710KL"))
      (libsource (lib "eagle-import") (part "RESISTOR0603"))
    )
    (comp (ref "TP1")
      (value "TPTP10R")
      (footprint "eagle-import:TP10R")
      (libsource (lib "eagle-import") (part "TPTP10R"))
    )
    (comp (ref "TP2")
      (value "TPTP08R")
      (footprint "eagle-import:TP08R")
      (libsource (lib "eagle-import") (part "TPTP08R"))
    )
    (comp (ref "TP3")
      (value "TPTP08R")
      (footprint "eagle-import:TP08R")
      (libsource (lib "eagle-import") (part "TPTP08R"))
    )
    (comp (ref "TP4")
      (value "TPTP08R")
      (footprint "eagle-import:TP08R")
      (libsource (lib "eagle-import") (part "TPTP08R"))
    )
    (comp (ref "TP5")
      (value "TPTP08R")
      (footprint "eagle-import:TP08R")
      (libsource (lib "eagle-import") (part "TPTP08R"))
    )
    (comp (ref "TP6")
      (value "TPTP08R")
      (footprint "eagle-import:TP08R")
      (libsource (lib "eagle-import") (part "TPTP08R"))
    )
    (comp (ref "TP7")
      (value "TPTP08R")
      (footprint "eagle-import:TP08R")
      (libsource (lib "eagle-import") (part "TPTP08R"))
    )
    (comp (ref "TP8")
      (value "TPTP08R")
      (footprint "eagle-import:TP08R")
      (libsource (lib "eagle-import") (part "TPTP08R"))
    )
    (comp (ref "TP9")
      (value "TPTP08R")
      (footprint "eagle-import:TP08R")
      (libsource (lib "eagle-import") (part "TPTP08R"))
    )
    (comp (ref "U15")
      (value "SKY13330-397LF")
      (footprint "eagle-import:QFN12")
      (libsource (lib "eagle-import") (part "SKYWORKS-13330397LF"))
    )
    (comp (ref "C26")
      (value ".1uF")
      (footprint "eagle-import:0603")
      (fields (field (name "PARTNO") "EMK107B7104KAHT"))
      (libsource (lib "eagle-import") (part "CAPACITOR0603"))
    )
    (comp (ref "C27")
      (value ".1uF")
      (footprint "eagle-import:0603")
      (fields (field (name "PARTNO") "EMK107B7104KAHT"))
      (libsource (lib "eagle-import") (part "CAPACITOR0603"))
    )
    (comp (ref "C28")
      (value ".1uF")
      (footprint "eagle-import:0603")
      (fields (field (name "PARTNO") "EMK107B7104KAHT"))
      (libsource (lib "eagle-import") (part "CAPACITOR0603"))
    )
    (comp (ref "C46")
      (value ".1uF")
      (footprint "eagle-import:0603")
      (fields (field (name "PARTNO") "EMK107B7104KAHT"))
      (libsource (lib "eagle-import") (part "CAPACITOR0603"))
    )
    (comp (ref "JLINK")
      (value "M05PTH")
      (footprint "eagle-import:1X05")
      (libsource (lib "eagle-import") (part "M05PTH"))
    )
    (comp (ref "NRST")
      (value "TPTP12R")
      (footprint "eagle-import:TP12R")
      (libsource (lib "eagle-import") (part "TPTP12R"))
    )
    (comp (ref "R2")
      (value "1k1")
      (footprint "eagle-import:0603")
      (fields (field (name "PARTNO") "RC0603JR-071K1L"))
      (libsource (lib "eagle-import") (part "RESISTOR0603"))
    )
    (comp (ref "R3")
      (value "1k1")
      (footprint "eagle-import:0603")
      (fields (field (name "PARTNO") "RC0603JR-071K1L"))
      (libsource (lib "eagle-import") (part "RESISTOR0603"))
    )
    (comp (ref "R7")
      (value "1k1")
      (footprint "eagle-import:0603")
      (fields (field (name "PARTNO") "RC0603JR-071K1L"))
      (libsource (lib "eagle-import") (part "RESISTOR0603"))
    )
    (comp (ref "R23")
      (value "10k")
      (footprint "eagle-import:0603")
      (fields (field (name "PARTNO") "RC0603JR-0710KL"))
      (libsource (lib "eagle-import") (part "RESISTOR0603"))
    )
    (comp (ref "RX")
      (value "TPTP12R")
      (footprint "eagle-import:TP12R")
      (libsource (lib "eagle-import") (part "TPTP12R"))
    )
    (comp (ref "S1")
      (value "KMR221NGLFS")
      (footprint "eagle-import:KMR221NGLFS")
      (libsource (lib "eagle-import") (part "KMR221NGLFS"))
    )
    (comp (ref "SWCLK")
      (value "TPTP12R")
      (footprint "eagle-import:TP12R")
      (libsource (lib "eagle-import") (part "TPTP12R"))
    )
    (comp (ref "SWDIO")
      (value "TPTP12R")
      (footprint "eagle-import:TP12R")
      (libsource (lib "eagle-import") (part "TPTP12R"))
    )
    (comp (ref "TX")
      (value "TPTP12R")
      (footprint "eagle-import:TP12R")
      (libsource (lib "eagle-import") (part "TPTP12R"))
    )
    (comp (ref "TX_OFF")
      (value "TPTP12R")
      (footprint "eagle-import:TP12R")
      (libsource (lib "eagle-import") (part "TPTP12R"))
    )
    (comp (ref "U6")
      (value "24LC01B")
      (footprint "eagle-import:SOT23-5")
      (fields (field (name "PARTNO") "24LC01BT-I/OT"))
      (libsource (lib "eagle-import") (part "24LC01B"))
    )
    (comp (ref "U13")
      (value "STM32L412K8U6")
      (footprint "eagle-import:QFN32")
      (libsource (lib "eagle-import") (part "STM32L432KXXX"))
    )
  )
  (nets
    (net (code "1") (name "1V8") (class "Default")
      (node (ref "1V8") (pin "TP") (pinfunction "TP_TP") (pintype "input"))
      (node (ref "C9") (pin "P$1") (pinfunction "1_P$1") (pintype "passive"))
      (node (ref "R14") (pin "P$2") (pinfunction "P$2_P$2") (pintype "passive"))
      (node (ref "R15") (pin "P$2") (pinfunction "P$2_P$2") (pintype "passive"))
      (node (ref "R19") (pin "P$2") (pinfunction "P$2_P$2") (pintype "passive"))
      (node (ref "U15") (pin "P$8") (pinfunction "EN_P$8") (pintype "bidirectional"))
      (node (ref "U4") (pin "6") (pinfunction "D_6") (pintype "bidirectional"))
      (node (ref "U5") (pin "5") (pinfunction "OUT_5") (pintype "passive"))
      (node (ref "U8") (pin "P$19") (pinfunction "V18_P$19") (pintype "bidirectional"))
      (node (ref "U8") (pin "P$3") (pinfunction "V18_P$3") (pintype "bidirectional"))
      (node (ref "U9") (pin "2") (pinfunction "G_2") (pintype "bidirectional"))
    )
    (net (code "2") (name "3.3V") (class "Default")
      (node (ref "3V3") (pin "TP") (pinfunction "TP_TP") (pintype "input"))
      (node (ref "C1") (pin "P$1") (pinfunction "1_P$1") (pintype "passive"))
      (node (ref "C26") (pin "P$1") (pinfunction "1_P$1") (pintype "passive"))
      (node (ref "C27") (pin "P$1") (pinfunction "1_P$1") (pintype "passive"))
      (node (ref "C28") (pin "P$1") (pinfunction "1_P$1") (pintype "passive"))
      (node (ref "C46") (pin "P$1") (pinfunction "1_P$1") (pintype "passive"))
      (node (ref "C8") (pin "P$1") (pinfunction "1_P$1") (pintype "passive"))
      (node (ref "JLINK") (pin "5") (pinfunction "5_5") (pintype "passive"))
      (node (ref "L12") (pin "P$2") (pinfunction "2_P$2") (pintype "passive"))
      (node (ref "L18") (pin "P$1") (pinfunction "1_P$1") (pintype "passive"))
      (node (ref "L19") (pin "P$1") (pinfunction "1_P$1") (pintype "passive"))
      (node (ref "Q1") (pin "2") (pinfunction "S_2") (pintype "passive"))
      (node (ref "R16") (pin "P$2") (pinfunction "P$2_P$2") (pintype "passive"))
      (node (ref "U1") (pin "1") (pinfunction "FB_1") (pintype "bidirectional"))
      (node (ref "U13") (pin "1") (pinfunction "VDD_1") (pintype "bidirectional"))
      (node (ref "U13") (pin "17") (pinfunction "VDD_17") (pintype "bidirectional"))
      (node (ref "U13") (pin "5") (pinfunction "VDDA_5") (pintype "bidirectional"))
      (node (ref "U15") (pin "P$9") (pinfunction "VCC_P$9") (pintype "bidirectional"))
      (node (ref "U5") (pin "1") (pinfunction "IN_1") (pintype "input"))
      (node (ref "U5") (pin "3") (pinfunction "EN_3") (pintype "input"))
      (node (ref "U6") (pin "4") (pinfunction "VCC_4") (pintype "bidirectional"))
    )
    (net (code "3") (name "AIS_RX_EVT") (class "Default")
      (node (ref "JP1") (pin "7") (pinfunction "7_7") (pintype "bidirectional"))
      (node (ref "R2") (pin "P$1") (pinfunction "P$1_P$1") (pintype "passive"))
    )
    (net (code "4") (name "AIS_TX_EVT") (class "Default")
      (node (ref "JP1") (pin "5") (pinfunction "5_5") (pintype "bidirectional"))
      (node (ref "R3") (pin "P$2") (pinfunction "P$2_P$2") (pintype "passive"))
    )
    (net (code "5") (name "BOOT0") (class "Default")
      (node (ref "R23") (pin "P$1") (pinfunction "P$1_P$1") (pintype "passive"))
      (node (ref "U13") (pin "31") (pinfunction "BOOT0_31") (pintype "bidirectional"))
    )
    (net (code "6") (name "CS1") (class "Default")
      (node (ref "U11") (pin "15") (pinfunction "NSEL_15") (pintype "input"))
      (node (ref "U13") (pin "10") (pinfunction "PA4_10") (pintype "bidirectional"))
    )
    (net (code "7") (name "CS2") (class "Default")
      (node (ref "U12") (pin "15") (pinfunction "NSEL_15") (pintype "input"))
      (node (ref "U13") (pin "6") (pinfunction "PA0_6") (pintype "bidirectional"))
    )
    (net (code "8") (name "GND") (class "Default")
      (node (ref "C1") (pin "P$2") (pinfunction "2_P$2") (pintype "passive"))
      (node (ref "C10") (pin "P$1") (pinfunction "1_P$1") (pintype "passive"))
      (node (ref "C11") (pin "P$2") (pinfunction "2_P$2") (pintype "passive"))
      (node (ref "C12") (pin "P$1") (pinfunction "1_P$1") (pintype "passive"))
      (node (ref "C14") (pin "P$2") (pinfunction "2_P$2") (pintype "passive"))
      (node (ref "C15") (pin "P$2") (pinfunction "2_P$2") (pintype "passive"))
      (node (ref "C16") (pin "P$2") (pinfunction "2_P$2") (pintype "passive"))
      (node (ref "C17") (pin "P$2") (pinfunction "2_P$2") (pintype "passive"))
      (node (ref "C19") (pin "P$1") (pinfunction "1_P$1") (pintype "passive"))
      (node (ref "C21") (pin "P$2") (pinfunction "2_P$2") (pintype "passive"))
      (node (ref "C23") (pin "P$2") (pinfunction "2_P$2") (pintype "passive"))
      (node (ref "C24") (pin "P$2") (pinfunction "2_P$2") (pintype "passive"))
      (node (ref "C25") (pin "P$2") (pinfunction "2_P$2") (pintype "passive"))
      (node (ref "C26") (pin "P$2") (pinfunction "2_P$2") (pintype "passive"))
      (node (ref "C27") (pin "P$2") (pinfunction "2_P$2") (pintype "passive"))
      (node (ref "C28") (pin "P$2") (pinfunction "2_P$2") (pintype "passive"))
      (node (ref "C3") (pin "P$2") (pinfunction "2_P$2") (pintype "passive"))
      (node (ref "C30") (pin "P$2") (pinfunction "2_P$2") (pintype "passive"))
      (node (ref "C31") (pin "P$1") (pinfunction "1_P$1") (pintype "passive"))
      (node (ref "C32") (pin "P$2") (pinfunction "2_P$2") (pintype "passive"))
      (node (ref "C34") (pin "P$2") (pinfunction "2_P$2") (pintype "passive"))
      (node (ref "C36") (pin "P$2") (pinfunction "2_P$2") (pintype "passive"))
      (node (ref "C37") (pin "P$2") (pinfunction "2_P$2") (pintype "passive"))
      (node (ref "C39") (pin "P$2") (pinfunction "2_P$2") (pintype "passive"))
      (node (ref "C4") (pin "P$2") (pinfunction "2_P$2") (pintype "passive"))
      (node (ref "C42") (pin "P$2") (pinfunction "2_P$2") (pintype "passive"))
      (node (ref "C43") (pin "P$2") (pinfunction "2_P$2") (pintype "passive"))
      (node (ref "C46") (pin "P$2") (pinfunction "2_P$2") (pintype "passive"))
      (node (ref "C47") (pin "P$2") (pinfunction "2_P$2") (pintype "passive"))
      (node (ref "C49") (pin "P$2") (pinfunction "2_P$2") (pintype "passive"))
      (node (ref "C50") (pin "P$1") (pinfunction "P$1_P$1") (pintype "bidirectional"))
      (node (ref "C50") (pin "P$2") (pinfunction "P$2_P$2") (pintype "bidirectional"))
      (node (ref "C52") (pin "P$2") (pinfunction "2_P$2") (pintype "passive"))
      (node (ref "C53") (pin "P$2") (pinfunction "2_P$2") (pintype "passive"))
      (node (ref "C6") (pin "P$2") (pinfunction "2_P$2") (pintype "passive"))
      (node (ref "C7") (pin "P$2") (pinfunction "2_P$2") (pintype "passive"))
      (node (ref "C8") (pin "P$2") (pinfunction "2_P$2") (pintype "passive"))
      (node (ref "C9") (pin "P$2") (pinfunction "2_P$2") (pintype "passive"))
      (node (ref "D3") (pin "A") (pinfunction "A_A") (pintype "passive"))
      (node (ref "GND1") (pin "TP") (pinfunction "TP_TP") (pintype "input"))
      (node (ref "GND2") (pin "TP") (pinfunction "TP_TP") (pintype "input"))
      (node (ref "J$1") (pin "GND@0") (pinfunction "GND_GND@0") (pintype "bidirectional"))
      (node (ref "J$1") (pin "GND@1") (pinfunction "GND_GND@1") (pintype "bidirectional"))
      (node (ref "J$1") (pin "GND@2") (pinfunction "GND_GND@2") (pintype "bidirectional"))
      (node (ref "J$1") (pin "GND@3") (pinfunction "GND_GND@3") (pintype "bidirectional"))
      (node (ref "JLINK") (pin "1") (pinfunction "1_1") (pintype "passive"))
      (node (ref "JP1") (pin "8") (pinfunction "8_8") (pintype "bidirectional"))
      (node (ref "Q2") (pin "1") (pinfunction "G_1") (pintype "passive"))
      (node (ref "R10") (pin "P$1") (pinfunction "P$1_P$1") (pintype "passive"))
      (node (ref "R12") (pin "P$1") (pinfunction "P$1_P$1") (pintype "passive"))
      (node (ref "R23") (pin "P$2") (pinfunction "P$2_P$2") (pintype "passive"))
      (node (ref "R4") (pin "P$1") (pinfunction "P$1_P$1") (pintype "passive"))
      (node (ref "R9") (pin "P$1") (pinfunction "P$1_P$1") (pintype "passive"))
      (node (ref "S1") (pin "P$2") (pinfunction "S2_P$2") (pintype "bidirectional"))
      (node (ref "TP2") (pin "TP") (pinfunction "TP_TP") (pintype "input"))
      (node (ref "TP3") (pin "TP") (pinfunction "TP_TP") (pintype "input"))
      (node (ref "TP4") (pin "TP") (pinfunction "TP_TP") (pintype "input"))
      (node (ref "TP5") (pin "TP") (pinfunction "TP_TP") (pintype "input"))
      (node (ref "TP6") (pin "TP") (pinfunction "TP_TP") (pintype "input"))
      (node (ref "TP7") (pin "TP") (pinfunction "TP_TP") (pintype "input"))
      (node (ref "TP8") (pin "TP") (pinfunction "TP_TP") (pintype "input"))
      (node (ref "TP9") (pin "TP") (pinfunction "TP_TP") (pintype "input"))
      (node (ref "U1") (pin "4") (pinfunction "GND_4") (pintype "bidirectional"))
      (node (ref "U11") (pin "EXP") (pinfunction "PAD_EXP") (pintype "bidirectional"))
      (node (ref "U12") (pin "EXP") (pinfunction "PAD_EXP") (pintype "bidirectional"))
      (node (ref "U13") (pin "16") (pinfunction "VSS_16") (pintype "bidirectional"))
      (node (ref "U13") (pin "32") (pinfunction "VSS_32") (pintype "bidirectional"))
      (node (ref "U13") (pin "EXP") (pinfunction "PAD_EXP") (pintype "bidirectional"))
      (node (ref "U15") (pin "P$1") (pinfunction "GND_P$1") (pintype "bidirectional"))
      (node (ref "U15") (pin "P$10") (pinfunction "GND_P$10") (pintype "bidirectional"))
      (node (ref "U15") (pin "P$12") (pinfunction "GND_P$12") (pintype "bidirectional"))
      (node (ref "U15") (pin "P$13") (pinfunction "GND_P$13") (pintype "bidirectional"))
      (node (ref "U15") (pin "P$3") (pinfunction "GND_P$3") (pintype "bidirectional"))
      (node (ref "U15") (pin "P$4") (pinfunction "GND_P$4") (pintype "bidirectional"))
      (node (ref "U15") (pin "P$6") (pinfunction "GND_P$6") (pintype "bidirectional"))
      (node (ref "U16") (pin "P$1") (pinfunction "GND_P$1") (pintype "bidirectional"))
      (node (ref "U16") (pin "P$3") (pinfunction "GND_P$3") (pintype "bidirectional"))
      (node (ref "U16") (pin "P$4") (pinfunction "GND_P$4") (pintype "bidirectional"))
      (node (ref "U16") (pin "P$6") (pinfunction "GND_P$6") (pintype "bidirectional"))
      (node (ref "U2") (pin "2") (pinfunction "GND_2") (pintype "bidirectional"))
      (node (ref "U2") (pin "4") (pinfunction "GND_4") (pintype "bidirectional"))
      (node (ref "U3") (pin "P$4") (pinfunction "GND_P$4") (pintype "bidirectional"))
      (node (ref "U3") (pin "P$7") (pinfunction "GND_P$7") (pintype "bidirectional"))
      (node (ref "U4") (pin "4") (pinfunction "S_4") (pintype "bidirectional"))
      (node (ref "U5") (pin "2") (pinfunction "GND_2") (pintype "input"))
      (node (ref "U6") (pin "2") (pinfunction "GND_2") (pintype "bidirectional"))
      (node (ref "U6") (pin "5") (pinfunction "WP_5") (pintype "bidirectional"))
      (node (ref "U7") (pin "2") (pinfunction "S_2") (pintype "passive"))
      (node (ref "U7") (pin "2@1") (pinfunction "PAD_2@1") (pintype "bidirectional"))
      (node (ref "U8") (pin "P$10") (pinfunction "GND_P$10") (pintype "bidirectional"))
      (node (ref "U8") (pin "P$2") (pinfunction "GND_P$2") (pintype "bidirectional"))
      (node (ref "U8") (pin "P$20") (pinfunction "GND_P$20") (pintype "bidirectional"))
      (node (ref "U9") (pin "4") (pinfunction "S_4") (pintype "bidirectional"))
      (node (ref "X1") (pin "2") (pinfunction "G2_2") (pintype "power_in"))
      (node (ref "X1") (pin "4") (pinfunction "G1_4") (pintype "power_in"))
      (node (ref "X2") (pin "2") (pinfunction "G2_2") (pintype "power_in"))
      (node (ref "X2") (pin "4") (pinfunction "G1_4") (pintype "power_in"))
    )
    (net (code "9") (name "GNSS_1PPS") (class "Default")
      (node (ref "U8") (pin "P$11") (pinfunction "TM_P$11") (pintype "bidirectional"))
      (node (ref "U9") (pin "5") (pinfunction "G_5") (pintype "bidirectional"))
    )
    (net (code "10") (name "GNSS_EN") (class "Default")
      (node (ref "R9") (pin "P$2") (pinfunction "P$2_P$2") (pintype "passive"))
      (node (ref "U13") (pin "2") (pinfunction "OSC_IN/PC14_2") (pintype "bidirectional"))
      (node (ref "U4") (pin "2") (pinfunction "G_2") (pintype "bidirectional"))
    )
    (net (code "11") (name "GNSS_EN_1V8") (class "Default")
      (node (ref "R10") (pin "P$2") (pinfunction "P$2_P$2") (pintype "passive"))
      (node (ref "U4") (pin "1") (pinfunction "S_1") (pintype "bidirectional"))
      (node (ref "U8") (pin "P$6") (pinfunction "ON_OFF_P$6") (pintype "bidirectional"))
    )
    (net (code "12") (name "GNSS_STATE") (class "Default")
      (node (ref "JP1") (pin "2") (pinfunction "2_2") (pintype "bidirectional"))
      (node (ref "R7") (pin "P$2") (pinfunction "P$2_P$2") (pintype "passive"))
    )
    (net (code "13") (name "GNSS_UART_TX") (class "Default")
      (node (ref "R15") (pin "P$1") (pinfunction "P$1_P$1") (pintype "passive"))
      (node (ref "U8") (pin "P$15") (pinfunction "TX_P$15") (pintype "bidirectional"))
      (node (ref "U9") (pin "1") (pinfunction "S_1") (pintype "bidirectional"))
    )
    (net (code "14") (name "I2C_SCL") (class "Default")
      (node (ref "U13") (pin "29") (pinfunction "PB6_29") (pintype "bidirectional"))
      (node (ref "U6") (pin "1") (pinfunction "SCL_1") (pintype "bidirectional"))
    )
    (net (code "15") (name "I2C_SDA") (class "Default")
      (node (ref "U13") (pin "30") (pinfunction "PB7_30") (pintype "bidirectional"))
      (node (ref "U6") (pin "3") (pinfunction "SDA_3") (pintype "bidirectional"))
    )
    (net (code "16") (name "MCU_GNSS_1PPS") (class "Default")
      (node (ref "U13") (pin "8") (pinfunction "PA2_8") (pintype "bidirectional"))
      (node (ref "U9") (pin "3") (pinfunction "D_3") (pintype "bidirectional"))
    )
    (net (code "17") (name "MCU_GNSS_UART_RX") (class "Default")
      (node (ref "R16") (pin "P$1") (pinfunction "P$1_P$1") (pintype "passive"))
      (node (ref "U13") (pin "9") (pinfunction "PA3_9") (pintype "bidirectional"))
      (node (ref "U9") (pin "6") (pinfunction "D_6") (pintype "bidirectional"))
    )
    (net (code "18") (name "MCU_UART_RX") (class "Default")
      (node (ref "JP1") (pin "3") (pinfunction "3_3") (pintype "bidirectional"))
      (node (ref "RX") (pin "TP") (pinfunction "TP_TP") (pintype "input"))
      (node (ref "U13") (pin "20") (pinfunction "PA10_20") (pintype "bidirectional"))
    )
    (net (code "19") (name "MCU_UART_TX") (class "Default")
      (node (ref "JP1") (pin "6") (pinfunction "6_6") (pintype "bidirectional"))
      (node (ref "TX") (pin "TP") (pinfunction "TP_TP") (pintype "input"))
      (node (ref "U13") (pin "19") (pinfunction "PA9_19") (pintype "bidirectional"))
    )
    (net (code "20") (name "MISO") (class "Default")
      (node (ref "U11") (pin "13") (pinfunction "SDO_13") (pintype "output"))
      (node (ref "U12") (pin "13") (pinfunction "SDO_13") (pintype "output"))
      (node (ref "U13") (pin "12") (pinfunction "PA6_12") (pintype "bidirectional"))
    )
    (net (code "21") (name "MOSI") (class "Default")
      (node (ref "U11") (pin "14") (pinfunction "SDI_14") (pintype "input"))
      (node (ref "U12") (pin "14") (pinfunction "SDI_14") (pintype "input"))
      (node (ref "U13") (pin "13") (pinfunction "PA7_13") (pintype "bidirectional"))
    )
    (net (code "22") (name "NRST") (class "Default")
      (node (ref "JLINK") (pin "2") (pinfunction "2_2") (pintype "passive"))
      (node (ref "NRST") (pin "TP") (pinfunction "TP_TP") (pintype "input"))
      (node (ref "S1") (pin "P$1") (pinfunction "S1_P$1") (pintype "bidirectional"))
      (node (ref "U13") (pin "4") (pinfunction "NRST_4") (pintype "bidirectional"))
    )
    (net (code "23") (name "Net-(C2-1)") (class "Default")
      (node (ref "C2") (pin "P$1") (pinfunction "1_P$1") (pintype "passive"))
      (node (ref "U1") (pin "6") (pinfunction "BST_6") (pintype "bidirectional"))
    )
    (net (code "24") (name "Net-(C2-2)") (class "Default")
      (node (ref "C2") (pin "P$2") (pinfunction "2_P$2") (pintype "passive"))
      (node (ref "L12") (pin "P$1") (pinfunction "1_P$1") (pintype "passive"))
      (node (ref "U1") (pin "5") (pinfunction "SW_5") (pintype "bidirectional"))
    )
    (net (code "25") (name "Net-(C5-1)") (class "Default")
      (node (ref "C5") (pin "P$1") (pinfunction "1_P$1") (pintype "passive"))
      (node (ref "L24") (pin "P$2") (pinfunction "2_P$2") (pintype "passive"))
      (node (ref "U2") (pin "1") (pinfunction "RF-OUT_1") (pintype "bidirectional"))
    )
    (net (code "26") (name "Net-(C5-2)") (class "Default")
      (node (ref "C5") (pin "P$2") (pinfunction "2_P$2") (pintype "passive"))
      (node (ref "L15") (pin "P$2") (pinfunction "2_P$2") (pintype "passive"))
    )
    (net (code "27") (name "Net-(C11-1)") (class "Default")
      (node (ref "C11") (pin "P$1") (pinfunction "1_P$1") (pintype "passive"))
      (node (ref "L17") (pin "P$2") (pinfunction "2_P$2") (pintype "passive"))
      (node (ref "R11") (pin "P$1") (pinfunction "P$1_P$1") (pintype "passive"))
      (node (ref "R12") (pin "P$2") (pinfunction "P$2_P$2") (pintype "passive"))
    )
    (net (code "28") (name "Net-(C14-1)") (class "Default")
      (node (ref "C14") (pin "P$1") (pinfunction "1_P$1") (pintype "passive"))
      (node (ref "C17") (pin "P$1") (pinfunction "1_P$1") (pintype "passive"))
      (node (ref "C34") (pin "P$1") (pinfunction "1_P$1") (pintype "passive"))
      (node (ref "L19") (pin "P$2") (pinfunction "2_P$2") (pintype "passive"))
      (node (ref "U12") (pin "6") (pinfunction "VDD_1_6") (pintype "power_in"))
      (node (ref "U12") (pin "8") (pinfunction "VDD_2_8") (pintype "power_in"))
    )
    (net (code "29") (name "Net-(C15-1)") (class "Default")
      (node (ref "C15") (pin "P$1") (pinfunction "1_P$1") (pintype "passive"))
      (node (ref "C16") (pin "P$1") (pinfunction "1_P$1") (pintype "passive"))
      (node (ref "C32") (pin "P$1") (pinfunction "1_P$1") (pintype "passive"))
      (node (ref "L18") (pin "P$2") (pinfunction "2_P$2") (pintype "passive"))
      (node (ref "R22") (pin "P$2") (pinfunction "P$2_P$2") (pintype "passive"))
      (node (ref "U11") (pin "6") (pinfunction "VDD_1_6") (pintype "power_in"))
      (node (ref "U11") (pin "8") (pinfunction "VDD_2_8") (pintype "power_in"))
    )
    (net (code "30") (name "Net-(C18-1)") (class "Default")
      (node (ref "C18") (pin "P$1") (pinfunction "1_P$1") (pintype "passive"))
      (node (ref "L8") (pin "P$1") (pinfunction "1_P$1") (pintype "passive"))
      (node (ref "U11") (pin "2") (pinfunction "RXP_2") (pintype "input"))
    )
    (net (code "31") (name "Net-(C19-2)") (class "Default")
      (node (ref "C19") (pin "P$2") (pinfunction "2_P$2") (pintype "passive"))
      (node (ref "L8") (pin "P$2") (pinfunction "2_P$2") (pintype "passive"))
      (node (ref "U11") (pin "3") (pinfunction "RXN_3") (pintype "input"))
    )
    (net (code "32") (name "Net-(C20-1)") (class "Default")
      (node (ref "C20") (pin "P$1") (pinfunction "1_P$1") (pintype "passive"))
      (node (ref "L13") (pin "P$1") (pinfunction "1_P$1") (pintype "passive"))
      (node (ref "U12") (pin "2") (pinfunction "RXP_2") (pintype "input"))
    )
    (net (code "33") (name "Net-(C21-1)") (class "Default")
      (node (ref "C21") (pin "P$1") (pinfunction "1_P$1") (pintype "passive"))
      (node (ref "L5") (pin "P$1") (pinfunction "1_P$1") (pintype "passive"))
      (node (ref "R22") (pin "P$1") (pinfunction "P$1_P$1") (pintype "passive"))
    )
    (net (code "34") (name "Net-(C22-1)") (class "Default")
      (node (ref "C22") (pin "P$1") (pinfunction "1_P$1") (pintype "passive"))
      (node (ref "L5") (pin "P$2") (pinfunction "2_P$2") (pintype "passive"))
      (node (ref "U11") (pin "4") (pinfunction "TX_4") (pintype "output"))
    )
    (net (code "35") (name "Net-(C22-2)") (class "Default")
      (node (ref "C22") (pin "P$2") (pinfunction "2_P$2") (pintype "passive"))
      (node (ref "L1") (pin "P$1") (pinfunction "1_P$1") (pintype "passive"))
    )
    (net (code "36") (name "Net-(C23-1)") (class "Default")
      (node (ref "C23") (pin "P$1") (pinfunction "1_P$1") (pintype "passive"))
      (node (ref "L1") (pin "P$2") (pinfunction "2_P$2") (pintype "passive"))
      (node (ref "L6") (pin "P$1") (pinfunction "1_P$1") (pintype "passive"))
    )
    (net (code "37") (name "Net-(C24-1)") (class "Default")
      (node (ref "C24") (pin "P$1") (pinfunction "1_P$1") (pintype "passive"))
      (node (ref "L6") (pin "P$2") (pinfunction "2_P$2") (pintype "passive"))
      (node (ref "L7") (pin "P$1") (pinfunction "1_P$1") (pintype "passive"))
    )
    (net (code "38") (name "Net-(C25-1)") (class "Default")
      (node (ref "C25") (pin "P$1") (pinfunction "1_P$1") (pintype "passive"))
      (node (ref "L11") (pin "P$1") (pinfunction "1_P$1") (pintype "passive"))
      (node (ref "L7") (pin "P$2") (pinfunction "2_P$2") (pintype "passive"))
    )
    (net (code "39") (name "Net-(C29-2)") (class "Default")
      (node (ref "C29") (pin "P$2") (pinfunction "2_P$2") (pintype "passive"))
      (node (ref "C30") (pin "P$1") (pinfunction "1_P$1") (pintype "passive"))
      (node (ref "L3") (pin "P$1") (pinfunction "1_P$1") (pintype "passive"))
    )
    (net (code "40") (name "Net-(C31-2)") (class "Default")
      (node (ref "C31") (pin "P$2") (pinfunction "2_P$2") (pintype "passive"))
      (node (ref "L13") (pin "P$2") (pinfunction "2_P$2") (pintype "passive"))
      (node (ref "U12") (pin "3") (pinfunction "RXN_3") (pintype "input"))
    )
    (net (code "41") (name "Net-(C36-1)") (class "Default")
      (node (ref "C36") (pin "P$1") (pinfunction "1_P$1") (pintype "passive"))
      (node (ref "L10") (pin "P$1") (pinfunction "1_P$1") (pintype "passive"))
      (node (ref "L9") (pin "P$2") (pinfunction "2_P$2") (pintype "passive"))
    )
    (net (code "42") (name "Net-(C37-1)") (class "Default")
      (node (ref "C37") (pin "P$1") (pinfunction "1_P$1") (pintype "passive"))
      (node (ref "C39") (pin "P$1") (pinfunction "1_P$1") (pintype "passive"))
      (node (ref "L4") (pin "P$2") (pinfunction "2_P$2") (pintype "passive"))
      (node (ref "L9") (pin "P$1") (pinfunction "1_P$1") (pintype "passive"))
      (node (ref "U7") (pin "3") (pinfunction "D_3") (pintype "passive"))
    )
    (net (code "43") (name "Net-(C41-2)") (class "Default")
      (node (ref "C41") (pin "P$2") (pinfunction "2_P$2") (pintype "passive"))
      (node (ref "U2") (pin "3") (pinfunction "RF-IN_3") (pintype "bidirectional"))
    )
    (net (code "44") (name "Net-(C42-1)") (class "Default")
      (node (ref "C42") (pin "P$1") (pinfunction "1_P$1") (pintype "passive"))
      (node (ref "C52") (pin "P$1") (pinfunction "1_P$1") (pintype "passive"))
      (node (ref "L10") (pin "P$2") (pinfunction "2_P$2") (pintype "passive"))
      (node (ref "L23") (pin "P$1") (pinfunction "1_P$1") (pintype "passive"))
    )
    (net (code "45") (name "Net-(C43-1)") (class "Default")
      (node (ref "C43") (pin "P$1") (pinfunction "1_P$1") (pintype "passive"))
      (node (ref "C6") (pin "P$1") (pinfunction "1_P$1") (pintype "passive"))
      (node (ref "L2") (pin "P$2") (pinfunction "2_P$2") (pintype "passive"))
      (node (ref "U1") (pin "2") (pinfunction "EN_2") (pintype "bidirectional"))
      (node (ref "U1") (pin "3") (pinfunction "VIN_3") (pintype "bidirectional"))
    )
    (net (code "46") (name "Net-(C44-1)") (class "Default")
      (node (ref "C44") (pin "P$1") (pinfunction "1_P$1") (pintype "passive"))
      (node (ref "C53") (pin "P$1") (pinfunction "1_P$1") (pintype "passive"))
      (node (ref "L23") (pin "P$2") (pinfunction "2_P$2") (pintype "passive"))
    )
    (net (code "47") (name "Net-(C47-1)") (class "Default")
      (node (ref "C47") (pin "P$1") (pinfunction "1_P$1") (pintype "passive"))
      (node (ref "C50") (pin "P$3") (pinfunction "P$3_P$3") (pintype "bidirectional"))
      (node (ref "D1") (pin "C") (pinfunction "C_C") (pintype "passive"))
      (node (ref "D3") (pin "C") (pinfunction "C_C") (pintype "passive"))
      (node (ref "R1") (pin "P$2") (pinfunction "P$2_P$2") (pintype "passive"))
      (node (ref "U3") (pin "P$5") (pinfunction "EN_P$5") (pintype "bidirectional"))
      (node (ref "U3") (pin "P$6") (pinfunction "VIN_P$6") (pintype "bidirectional"))
    )
    (net (code "48") (name "Net-(D1-PadA)") (class "Default")
      (node (ref "D1") (pin "A") (pinfunction "A_A") (pintype "passive"))
      (node (ref "R6") (pin "P$2") (pinfunction "P$2_P$2") (pintype "passive"))
    )
    (net (code "49") (name "Net-(J$1-SIGNAL)") (class "Default")
      (node (ref "J$1") (pin "SIG") (pinfunction "SIGNAL_SIG") (pintype "bidirectional"))
      (node (ref "TP1") (pin "TP") (pinfunction "TP_TP") (pintype "input"))
      (node (ref "U15") (pin "P$2") (pinfunction "RF1_P$2") (pintype "bidirectional"))
    )
    (net (code "50") (name "Net-(L14-1)") (class "Default")
      (node (ref "L14") (pin "P$1") (pinfunction "1_P$1") (pintype "passive"))
      (node (ref "U16") (pin "P$2") (pinfunction "IN_P$2") (pintype "bidirectional"))
    )
    (net (code "51") (name "Net-(L14-2)") (class "Default")
      (node (ref "L14") (pin "P$2") (pinfunction "2_P$2") (pintype "passive"))
      (node (ref "L15") (pin "P$1") (pinfunction "1_P$1") (pintype "passive"))
    )
    (net (code "52") (name "Net-(L16-1)") (class "Default")
      (node (ref "L16") (pin "P$1") (pinfunction "1_P$1") (pintype "passive"))
      (node (ref "L20") (pin "P$2") (pinfunction "2_P$2") (pintype "passive"))
    )
    (net (code "53") (name "Net-(L16-2)") (class "Default")
      (node (ref "L16") (pin "P$2") (pinfunction "2_P$2") (pintype "passive"))
      (node (ref "U16") (pin "P$5") (pinfunction "OUT_P$5") (pintype "bidirectional"))
    )
    (net (code "54") (name "Net-(L17-1)") (class "Default")
      (node (ref "L17") (pin "P$1") (pinfunction "1_P$1") (pintype "passive"))
      (node (ref "L3") (pin "P$2") (pinfunction "2_P$2") (pintype "passive"))
      (node (ref "U7") (pin "1") (pinfunction "G_1") (pintype "passive"))
    )
    (net (code "55") (name "Net-(Q2-D)") (class "Default")
      (node (ref "JP1") (pin "1") (pinfunction "1_1") (pintype "bidirectional"))
      (node (ref "Q2") (pin "3") (pinfunction "D_3") (pintype "passive"))
      (node (ref "V_BAT") (pin "TP") (pinfunction "TP_TP") (pintype "input"))
    )
    (net (code "56") (name "Net-(U3-ADJ)") (class "Default")
      (node (ref "R4") (pin "P$2") (pinfunction "P$2_P$2") (pintype "passive"))
      (node (ref "R5") (pin "P$1") (pinfunction "P$1_P$1") (pintype "passive"))
      (node (ref "U3") (pin "P$2") (pinfunction "ADJ_P$2") (pintype "bidirectional"))
    )
    (net (code "57") (name "Net-(U8-GPIO6)") (class "Default")
      (node (ref "R14") (pin "P$1") (pinfunction "P$1_P$1") (pintype "passive"))
      (node (ref "U8") (pin "P$13") (pinfunction "GPIO6_P$13") (pintype "bidirectional"))
    )
    (net (code "58") (name "Net-(U10-RF)") (class "Default")
      (node (ref "U10") (pin "P$1") (pinfunction "RF_P$1") (pintype "bidirectional"))
      (node (ref "U8") (pin "P$1") (pinfunction "RF_IN_P$1") (pintype "bidirectional"))
    )
    (net (code "59") (name "Net-(U11-XIN)") (class "Default")
      (node (ref "U11") (pin "17") (pinfunction "XIN_17") (pintype "input"))
      (node (ref "X1") (pin "3") (pinfunction "X2_3") (pintype "bidirectional"))
    )
    (net (code "60") (name "Net-(U11-XOUT)") (class "Default")
      (node (ref "U11") (pin "16") (pinfunction "XOUT_16") (pintype "bidirectional"))
      (node (ref "X1") (pin "1") (pinfunction "X1_1") (pintype "bidirectional"))
    )
    (net (code "61") (name "Net-(U12-XIN)") (class "Default")
      (node (ref "U12") (pin "17") (pinfunction "XIN_17") (pintype "input"))
      (node (ref "X2") (pin "3") (pinfunction "X2_3") (pintype "bidirectional"))
    )
    (net (code "62") (name "Net-(U12-XOUT)") (class "Default")
      (node (ref "U12") (pin "16") (pinfunction "XOUT_16") (pintype "bidirectional"))
      (node (ref "X2") (pin "1") (pinfunction "X1_1") (pintype "bidirectional"))
    )
    (net (code "63") (name "Net-(U13-PA1)") (class "Default")
      (node (ref "R2") (pin "P$2") (pinfunction "P$2_P$2") (pintype "passive"))
      (node (ref "U13") (pin "7") (pinfunction "PA1_7") (pintype "bidirectional"))
    )
    (net (code "64") (name "Net-(U13-PA8)") (class "Default")
      (node (ref "R3") (pin "P$1") (pinfunction "P$1_P$1") (pintype "passive"))
      (node (ref "U13") (pin "18") (pinfunction "PA8_18") (pintype "bidirectional"))
    )
    (net (code "65") (name "Net-(U13-PA11)") (class "Default")
      (node (ref "R7") (pin "P$1") (pinfunction "P$1_P$1") (pintype "passive"))
      (node (ref "U13") (pin "21") (pinfunction "PA11_21") (pintype "bidirectional"))
    )
    (net (code "66") (name "Net-(U15-CTRL)") (class "Default")
      (node (ref "R19") (pin "P$1") (pinfunction "P$1_P$1") (pintype "passive"))
      (node (ref "U15") (pin "P$7") (pinfunction "CTRL_P$7") (pintype "bidirectional"))
      (node (ref "U4") (pin "3") (pinfunction "D_3") (pintype "bidirectional"))
    )
    (net (code "67") (name "PA_IN") (class "Default")
      (node (ref "C29") (pin "P$1") (pinfunction "1_P$1") (pintype "passive"))
      (node (ref "L11") (pin "P$2") (pinfunction "2_P$2") (pintype "passive"))
    )
    (net (code "68") (name "PA_OUT") (class "Default")
      (node (ref "C44") (pin "P$2") (pinfunction "2_P$2") (pintype "passive"))
      (node (ref "U15") (pin "P$5") (pinfunction "RF3_P$5") (pintype "bidirectional"))
    )
    (net (code "69") (name "RF_IN") (class "Default")
      (node (ref "C41") (pin "P$1") (pinfunction "1_P$1") (pintype "passive"))
      (node (ref "U15") (pin "P$11") (pinfunction "RF2_P$11") (pintype "bidirectional"))
    )
    (net (code "70") (name "RX_IC_CLK") (class "Default")
      (node (ref "U12") (pin "20") (pinfunction "GPIO3_20") (pintype "bidirectional"))
      (node (ref "U13") (pin "26") (pinfunction "PB3_26") (pintype "bidirectional"))
    )
    (net (code "71") (name "RX_IC_DATA") (class "Default")
      (node (ref "U12") (pin "10") (pinfunction "GPIO1_10") (pintype "bidirectional"))
      (node (ref "U13") (pin "27") (pinfunction "PB4_27") (pintype "bidirectional"))
    )
    (net (code "72") (name "RX_IN") (class "Default")
      (node (ref "C10") (pin "P$2") (pinfunction "2_P$2") (pintype "passive"))
      (node (ref "C18") (pin "P$2") (pinfunction "2_P$2") (pintype "passive"))
      (node (ref "C20") (pin "P$2") (pinfunction "2_P$2") (pintype "passive"))
      (node (ref "L20") (pin "P$1") (pinfunction "1_P$1") (pintype "passive"))
    )
    (net (code "73") (name "SCK") (class "Default")
      (node (ref "U11") (pin "12") (pinfunction "SCLK_12") (pintype "input"))
      (node (ref "U12") (pin "12") (pinfunction "SCLK_12") (pintype "input"))
      (node (ref "U13") (pin "11") (pinfunction "PA5_11") (pintype "bidirectional"))
    )
    (net (code "74") (name "SDN1") (class "Default")
      (node (ref "U11") (pin "1") (pinfunction "SDN_1") (pintype "input"))
      (node (ref "U13") (pin "14") (pinfunction "PB0_14") (pintype "bidirectional"))
    )
    (net (code "75") (name "SDN2") (class "Default")
      (node (ref "U12") (pin "1") (pinfunction "SDN_1") (pintype "input"))
      (node (ref "U13") (pin "25") (pinfunction "PA15_25") (pintype "bidirectional"))
    )
    (net (code "76") (name "SWCLK") (class "Default")
      (node (ref "JLINK") (pin "3") (pinfunction "3_3") (pintype "passive"))
      (node (ref "SWCLK") (pin "TP") (pinfunction "TP_TP") (pintype "input"))
      (node (ref "U13") (pin "24") (pinfunction "PA14_24") (pintype "bidirectional"))
    )
    (net (code "77") (name "SWDIO") (class "Default")
      (node (ref "JLINK") (pin "4") (pinfunction "4_4") (pintype "passive"))
      (node (ref "SWDIO") (pin "TP") (pinfunction "TP_TP") (pintype "input"))
      (node (ref "U13") (pin "23") (pinfunction "PA13_23") (pintype "bidirectional"))
    )
    (net (code "78") (name "TRX_IC_CLOCK") (class "Default")
      (node (ref "U11") (pin "19") (pinfunction "GPIO2_19") (pintype "bidirectional"))
      (node (ref "U13") (pin "3") (pinfunction "OSC_OUT/PC15_3") (pintype "bidirectional"))
    )
    (net (code "79") (name "TRX_IC_DATA") (class "Default")
      (node (ref "U11") (pin "10") (pinfunction "GPIO1_10") (pintype "bidirectional"))
      (node (ref "U13") (pin "15") (pinfunction "PB1_15") (pintype "bidirectional"))
    )
    (net (code "80") (name "TX_CTRL") (class "Default")
      (node (ref "Q1") (pin "1") (pinfunction "G_1") (pintype "passive"))
      (node (ref "R11") (pin "P$2") (pinfunction "P$2_P$2") (pintype "passive"))
      (node (ref "U13") (pin "28") (pinfunction "PB5_28") (pintype "bidirectional"))
      (node (ref "U4") (pin "5") (pinfunction "G_5") (pintype "bidirectional"))
    )
    (net (code "81") (name "TX_OFF") (class "Default")
      (node (ref "JP1") (pin "4") (pinfunction "4_4") (pintype "bidirectional"))
      (node (ref "TX_OFF") (pin "TP") (pinfunction "TP_TP") (pintype "input"))
      (node (ref "U13") (pin "22") (pinfunction "PA12_22") (pintype "bidirectional"))
    )
    (net (code "82") (name "V_IN") (class "Default")
      (node (ref "C4") (pin "P$1") (pinfunction "1_P$1") (pintype "passive"))
      (node (ref "L2") (pin "P$1") (pinfunction "1_P$1") (pintype "passive"))
      (node (ref "Q2") (pin "2") (pinfunction "S_2") (pintype "passive"))
      (node (ref "R1") (pin "P$1") (pinfunction "P$1_P$1") (pintype "passive"))
      (node (ref "R6") (pin "P$1") (pinfunction "P$1_P$1") (pintype "passive"))
    )
    (net (code "83") (name "V_LNA") (class "Default")
      (node (ref "C12") (pin "P$2") (pinfunction "2_P$2") (pintype "passive"))
      (node (ref "C3") (pin "P$1") (pinfunction "1_P$1") (pintype "passive"))
      (node (ref "L24") (pin "P$1") (pinfunction "1_P$1") (pintype "passive"))
      (node (ref "Q1") (pin "3") (pinfunction "D_3") (pintype "passive"))
    )
    (net (code "84") (name "V_PA") (class "Default")
      (node (ref "C49") (pin "P$1") (pinfunction "1_P$1") (pintype "passive"))
      (node (ref "C7") (pin "P$1") (pinfunction "1_P$1") (pintype "passive"))
      (node (ref "L4") (pin "P$1") (pinfunction "1_P$1") (pintype "passive"))
      (node (ref "R5") (pin "P$2") (pinfunction "P$2_P$2") (pintype "passive"))
      (node (ref "U3") (pin "P$1") (pinfunction "VOUT_P$1") (pintype "bidirectional"))
      (node (ref "V_PA") (pin "TP") (pinfunction "TP_TP") (pintype "input"))
    )
    (net (code "85") (name "unconnected-(S1-S1-PadP$4)") (class "Default")
      (node (ref "S1") (pin "P$4") (pinfunction "S1_P$4") (pintype "bidirectional"))
    )
    (net (code "86") (name "unconnected-(S1-S2-PadP$3)") (class "Default")
      (node (ref "S1") (pin "P$3") (pinfunction "S2_P$3") (pintype "bidirectional"))
    )
    (net (code "87") (name "unconnected-(U3-PG-PadP$3)") (class "Default")
      (node (ref "U3") (pin "P$3") (pinfunction "PG_P$3") (pintype "bidirectional"))
    )
    (net (code "88") (name "unconnected-(U5-BP-Pad4)") (class "Default")
      (node (ref "U5") (pin "4") (pinfunction "BP_4") (pintype "input"))
    )
    (net (code "89") (name "unconnected-(U8-BOOTSEL-PadP$9)") (class "Default")
      (node (ref "U8") (pin "P$9") (pinfunction "BOOTSEL_P$9") (pintype "bidirectional"))
    )
    (net (code "90") (name "unconnected-(U8-GPIO0-PadP$18)") (class "Default")
      (node (ref "U8") (pin "P$18") (pinfunction "GPIO0_P$18") (pintype "bidirectional"))
    )
    (net (code "91") (name "unconnected-(U8-GPIO1-PadP$17)") (class "Default")
      (node (ref "U8") (pin "P$17") (pinfunction "GPIO1_P$17") (pintype "bidirectional"))
    )
    (net (code "92") (name "unconnected-(U8-GPIO7-PadP$12)") (class "Default")
      (node (ref "U8") (pin "P$12") (pinfunction "GPIO7_P$12") (pintype "bidirectional"))
    )
    (net (code "93") (name "unconnected-(U8-GPIO8-PadP$5)") (class "Default")
      (node (ref "U8") (pin "P$5") (pinfunction "GPIO8_P$5") (pintype "bidirectional"))
    )
    (net (code "94") (name "unconnected-(U8-NC-PadP$4)") (class "Default")
      (node (ref "U8") (pin "P$4") (pinfunction "NC_P$4") (pintype "bidirectional"))
    )
    (net (code "95") (name "unconnected-(U8-NC-PadP$16)") (class "Default")
      (node (ref "U8") (pin "P$16") (pinfunction "NC_P$16") (pintype "bidirectional"))
    )
    (net (code "96") (name "unconnected-(U8-NRESET-PadP$8)") (class "Default")
      (node (ref "U8") (pin "P$8") (pinfunction "NRESET_P$8") (pintype "bidirectional"))
    )
    (net (code "97") (name "unconnected-(U8-RX-PadP$14)") (class "Default")
      (node (ref "U8") (pin "P$14") (pinfunction "RX_P$14") (pintype "bidirectional"))
    )
    (net (code "98") (name "unconnected-(U8-SYS_ON-PadP$7)") (class "Default")
      (node (ref "U8") (pin "P$7") (pinfunction "SYS_ON_P$7") (pintype "bidirectional"))
    )
    (net (code "99") (name "unconnected-(U10-PAD-PadP$2)") (class "Default")
      (node (ref "U10") (pin "P$2") (pinfunction "PAD_P$2") (pintype "bidirectional"))
    )
    (net (code "100") (name "unconnected-(U11-GNDX-Pad18)") (class "Default")
      (node (ref "U11") (pin "18") (pinfunction "GNDX_18") (pintype "bidirectional"))
    )
    (net (code "101") (name "unconnected-(U11-GPIO0-Pad9)") (class "Default")
      (node (ref "U11") (pin "9") (pinfunction "GPIO0_9") (pintype "bidirectional"))
    )
    (net (code "102") (name "unconnected-(U11-GPIO3-Pad20)") (class "Default")
      (node (ref "U11") (pin "20") (pinfunction "GPIO3_20") (pintype "bidirectional"))
    )
    (net (code "103") (name "unconnected-(U11-NIRQ-Pad11)") (class "Default")
      (node (ref "U11") (pin "11") (pinfunction "NIRQ_11") (pintype "bidirectional"))
    )
    (net (code "104") (name "unconnected-(U11-TXRAMP-Pad7)") (class "Default")
      (node (ref "U11") (pin "7") (pinfunction "TXRAMP_7") (pintype "bidirectional"))
    )
    (net (code "105") (name "unconnected-(U12-GNDX-Pad18)") (class "Default")
      (node (ref "U12") (pin "18") (pinfunction "GNDX_18") (pintype "bidirectional"))
    )
    (net (code "106") (name "unconnected-(U12-GPIO0-Pad9)") (class "Default")
      (node (ref "U12") (pin "9") (pinfunction "GPIO0_9") (pintype "bidirectional"))
    )
    (net (code "107") (name "unconnected-(U12-GPIO2-Pad19)") (class "Default")
      (node (ref "U12") (pin "19") (pinfunction "GPIO2_19") (pintype "bidirectional"))
    )
    (net (code "108") (name "unconnected-(U12-NIRQ-Pad11)") (class "Default")
      (node (ref "U12") (pin "11") (pinfunction "NIRQ_11") (pintype "bidirectional"))
    )
    (net (code "109") (name "unconnected-(U12-TX-Pad4)") (class "Default")
      (node (ref "U12") (pin "4") (pinfunction "TX_4") (pintype "output"))
    )
    (net (code "110") (name "unconnected-(U12-TXRAMP-Pad7)") (class "Default")
      (node (ref "U12") (pin "7") (pinfunction "TXRAMP_7") (pintype "bidirectional"))
    )
  )
)
